# timer_rtc_io.net
KiCad netlist of a schematic drawn in EAGLE
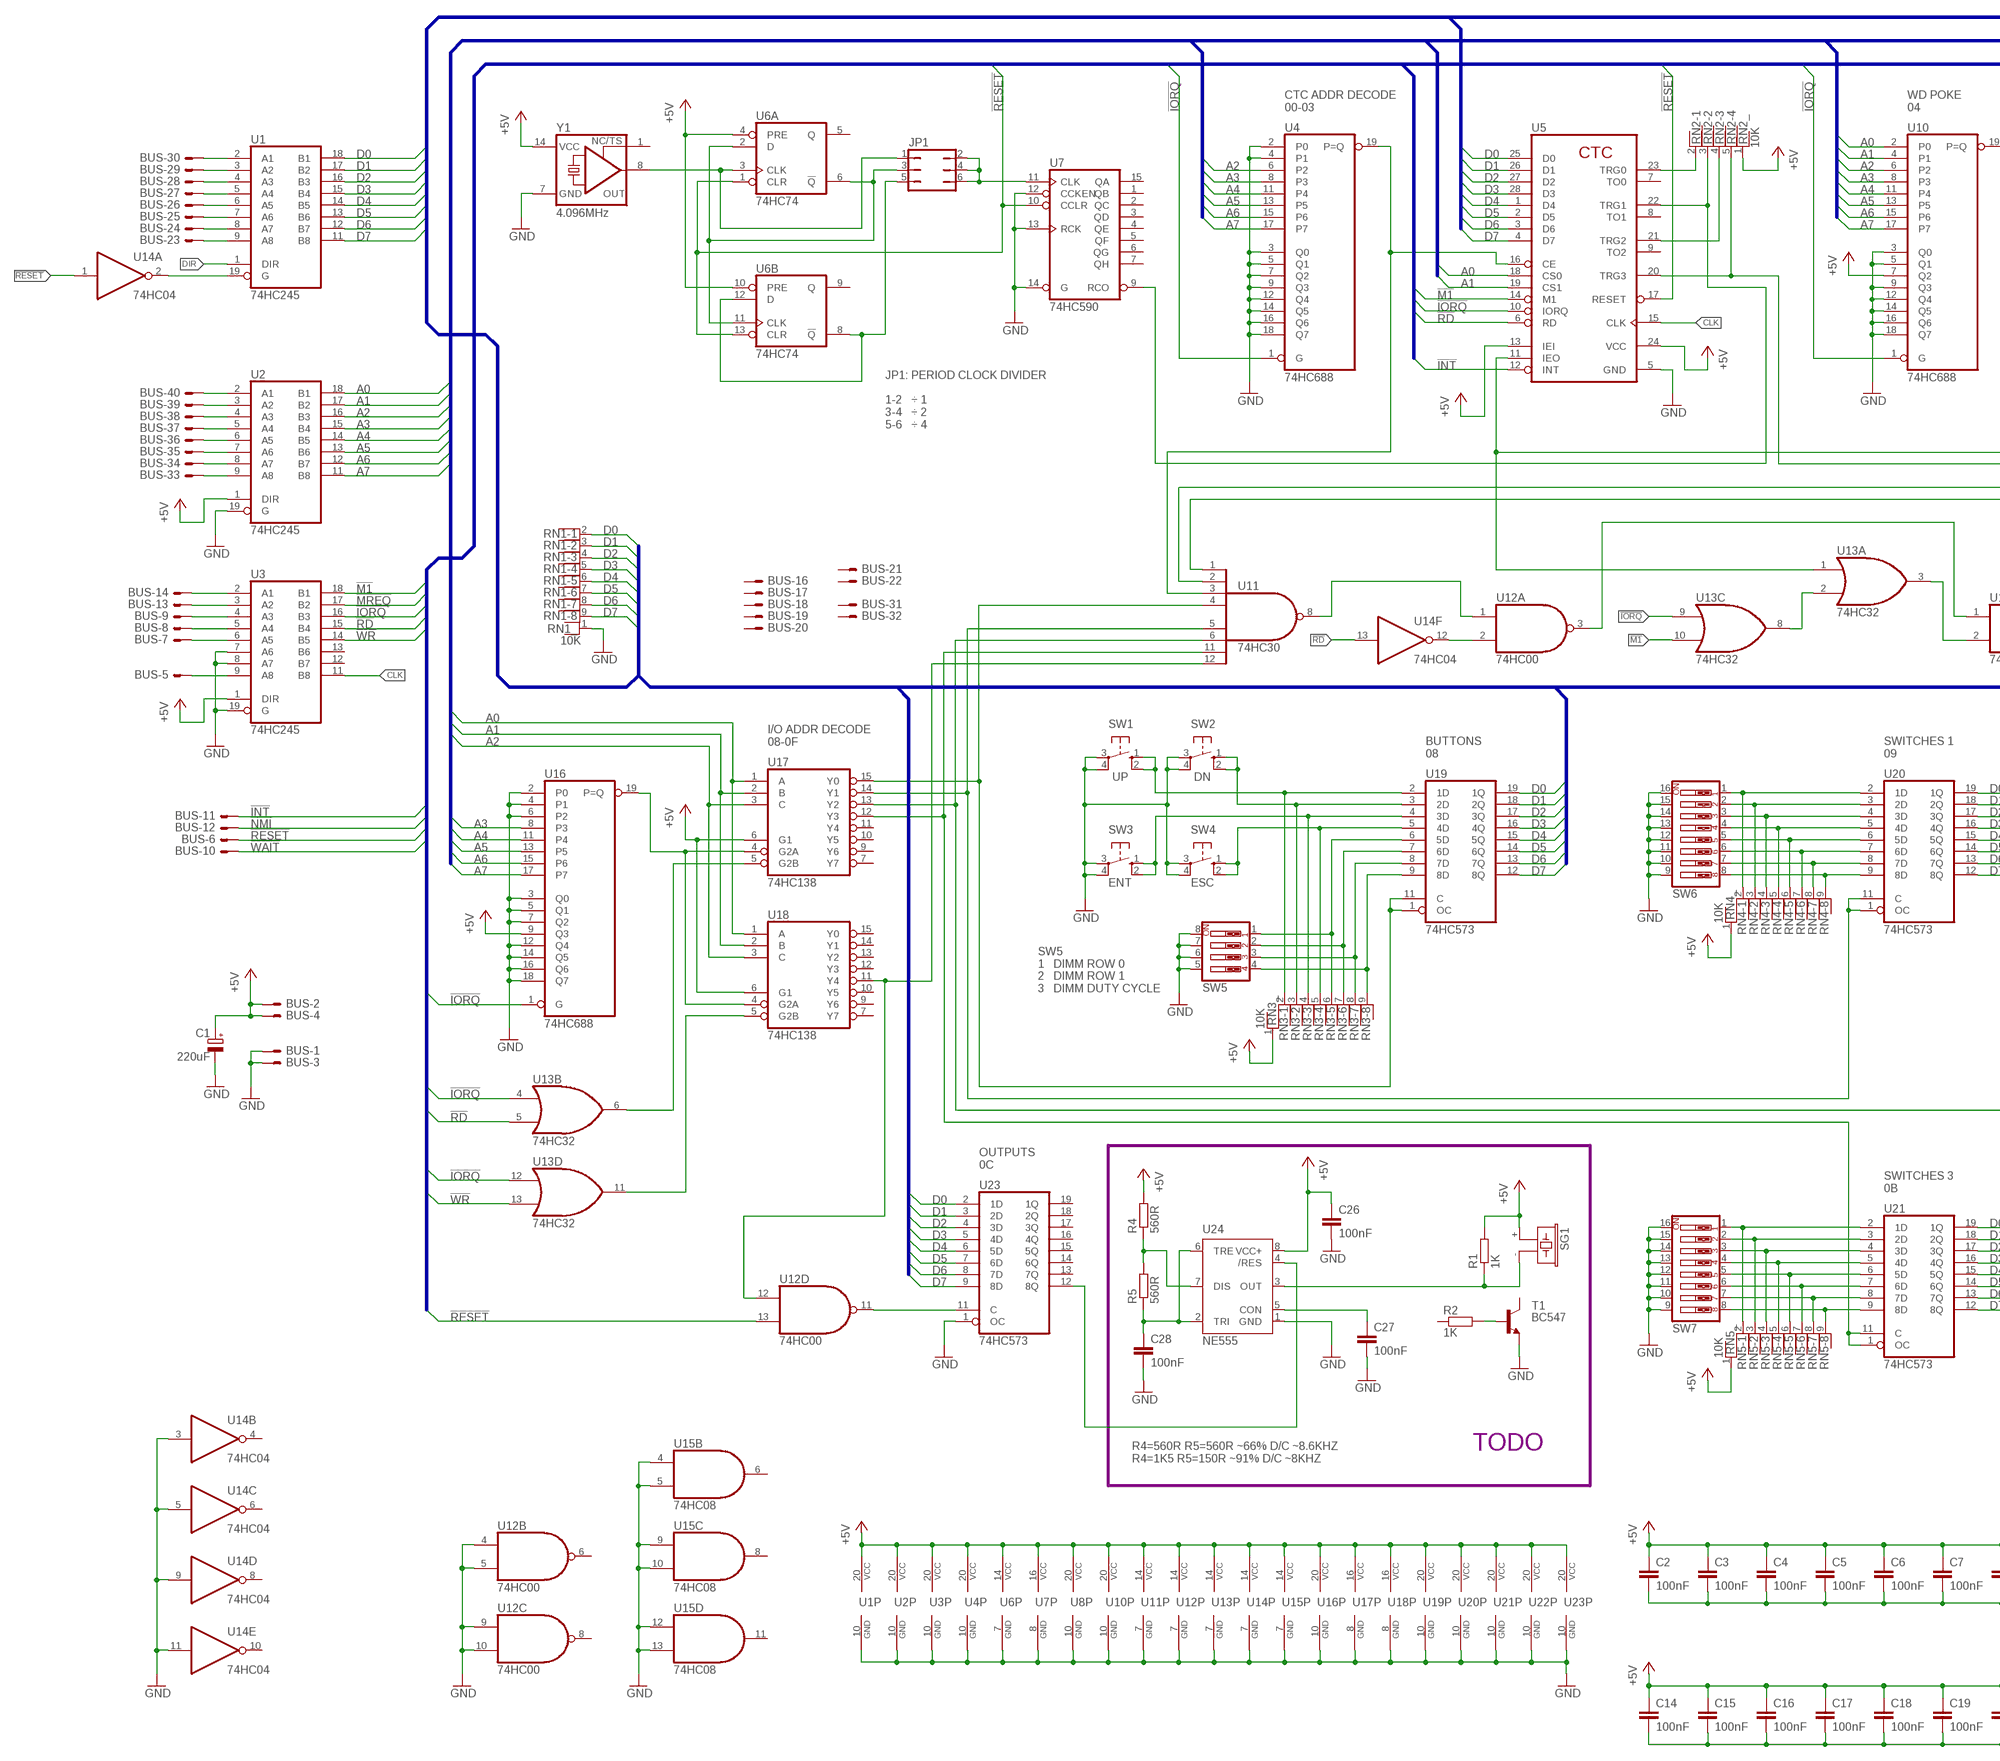
[diagram p0: schematic, sheet 1, part 1 of 2]
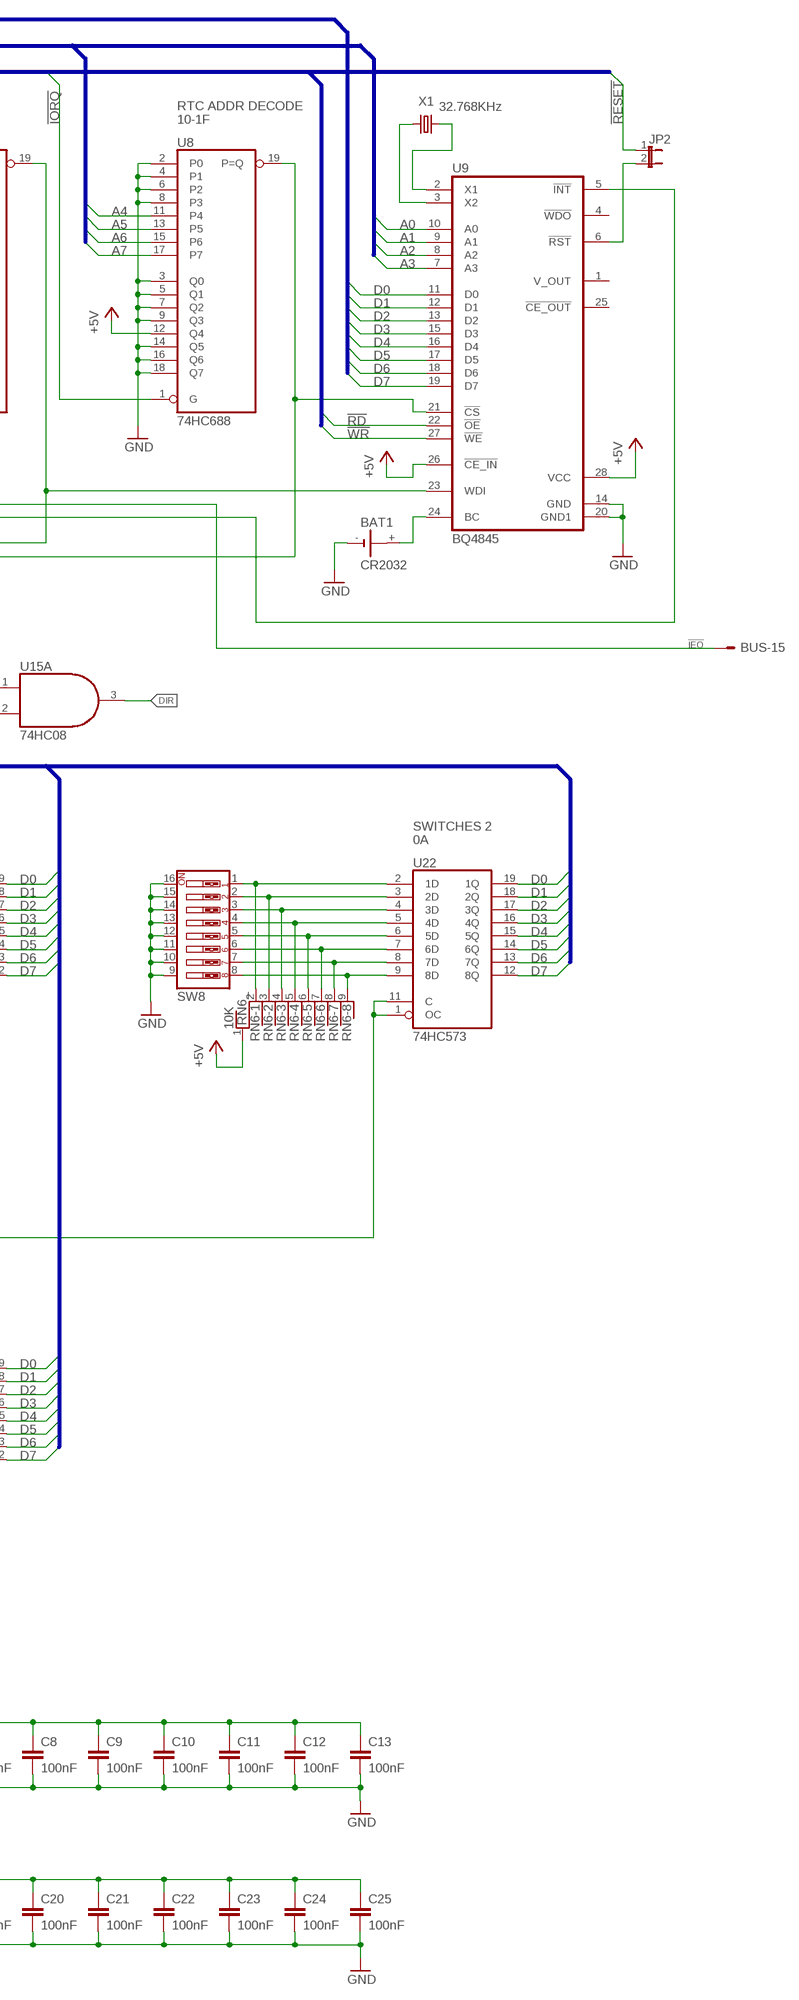
[diagram p1: schematic, sheet 1, part 2 of 2]

(export (version "E")
  (design (tool "Eeschema 10.0.6"))
  (components
    (comp (ref "BAT1")
      (value "CR2032")
      (footprint "eagle-import:CR2032H")
      (libsource (lib "eagle-import") (part "CR2032H"))
    )
    (comp (ref "BUS")
      (value "ML40E")
      (footprint "eagle-import:ML40")
      (libsource (lib "eagle-import") (part "ML40E"))
    )
    (comp (ref "C1")
      (value "220uF")
      (footprint "eagle-import:E3,5-8")
      (libsource (lib "eagle-import") (part "CPOL-EUE3.5-8"))
    )
    (comp (ref "C2")
      (value "100nF")
      (footprint "eagle-import:C050-025X075")
      (libsource (lib "eagle-import") (part "C-EU050-025X075"))
    )
    (comp (ref "C3")
      (value "100nF")
      (footprint "eagle-import:C050-025X075")
      (libsource (lib "eagle-import") (part "C-EU050-025X075"))
    )
    (comp (ref "C4")
      (value "100nF")
      (footprint "eagle-import:C050-025X075")
      (libsource (lib "eagle-import") (part "C-EU050-025X075"))
    )
    (comp (ref "C5")
      (value "100nF")
      (footprint "eagle-import:C050-025X075")
      (libsource (lib "eagle-import") (part "C-EU050-025X075"))
    )
    (comp (ref "C6")
      (value "100nF")
      (footprint "eagle-import:C050-025X075")
      (libsource (lib "eagle-import") (part "C-EU050-025X075"))
    )
    (comp (ref "C7")
      (value "100nF")
      (footprint "eagle-import:C050-025X075")
      (libsource (lib "eagle-import") (part "C-EU050-025X075"))
    )
    (comp (ref "C8")
      (value "100nF")
      (footprint "eagle-import:C050-025X075")
      (libsource (lib "eagle-import") (part "C-EU050-025X075"))
    )
    (comp (ref "C9")
      (value "100nF")
      (footprint "eagle-import:C050-025X075")
      (libsource (lib "eagle-import") (part "C-EU050-025X075"))
    )
    (comp (ref "C10")
      (value "100nF")
      (footprint "eagle-import:C050-025X075")
      (libsource (lib "eagle-import") (part "C-EU050-025X075"))
    )
    (comp (ref "C11")
      (value "100nF")
      (footprint "eagle-import:C050-025X075")
      (libsource (lib "eagle-import") (part "C-EU050-025X075"))
    )
    (comp (ref "C12")
      (value "100nF")
      (footprint "eagle-import:C050-025X075")
      (libsource (lib "eagle-import") (part "C-EU050-025X075"))
    )
    (comp (ref "C13")
      (value "100nF")
      (footprint "eagle-import:C050-025X075")
      (libsource (lib "eagle-import") (part "C-EU050-025X075"))
    )
    (comp (ref "C14")
      (value "100nF")
      (footprint "eagle-import:C050-025X075")
      (libsource (lib "eagle-import") (part "C-EU050-025X075"))
    )
    (comp (ref "C15")
      (value "100nF")
      (footprint "eagle-import:C050-025X075")
      (libsource (lib "eagle-import") (part "C-EU050-025X075"))
    )
    (comp (ref "C16")
      (value "100nF")
      (footprint "eagle-import:C050-025X075")
      (libsource (lib "eagle-import") (part "C-EU050-025X075"))
    )
    (comp (ref "C17")
      (value "100nF")
      (footprint "eagle-import:C050-025X075")
      (libsource (lib "eagle-import") (part "C-EU050-025X075"))
    )
    (comp (ref "C18")
      (value "100nF")
      (footprint "eagle-import:C050-025X075")
      (libsource (lib "eagle-import") (part "C-EU050-025X075"))
    )
    (comp (ref "C19")
      (value "100nF")
      (footprint "eagle-import:C050-025X075")
      (libsource (lib "eagle-import") (part "C-EU050-025X075"))
    )
    (comp (ref "C20")
      (value "100nF")
      (footprint "eagle-import:C050-025X075")
      (libsource (lib "eagle-import") (part "C-EU050-025X075"))
    )
    (comp (ref "C21")
      (value "100nF")
      (footprint "eagle-import:C050-025X075")
      (libsource (lib "eagle-import") (part "C-EU050-025X075"))
    )
    (comp (ref "C22")
      (value "100nF")
      (footprint "eagle-import:C050-025X075")
      (libsource (lib "eagle-import") (part "C-EU050-025X075"))
    )
    (comp (ref "C23")
      (value "100nF")
      (footprint "eagle-import:C050-025X075")
      (libsource (lib "eagle-import") (part "C-EU050-025X075"))
    )
    (comp (ref "C24")
      (value "100nF")
      (footprint "eagle-import:C050-025X075")
      (libsource (lib "eagle-import") (part "C-EU050-025X075"))
    )
    (comp (ref "C25")
      (value "100nF")
      (footprint "eagle-import:C050-025X075")
      (libsource (lib "eagle-import") (part "C-EU050-025X075"))
    )
    (comp (ref "C26")
      (value "100nF")
      (footprint "eagle-import:C050-025X075")
      (libsource (lib "eagle-import") (part "C-EU050-025X075"))
    )
    (comp (ref "C27")
      (value "100nF")
      (footprint "eagle-import:C050-025X075")
      (libsource (lib "eagle-import") (part "C-EU050-025X075"))
    )
    (comp (ref "C28")
      (value "100nF")
      (footprint "eagle-import:C050-025X075")
      (libsource (lib "eagle-import") (part "C-EU050-025X075"))
    )
    (comp (ref "JP1")
      (value "JP3Q")
      (footprint "eagle-import:JP3Q")
      (libsource (lib "eagle-import") (part "JP3Q"))
    )
    (comp (ref "JP2")
      (value "JP1E")
      (footprint "eagle-import:JP1")
      (libsource (lib "eagle-import") (part "JP1E"))
    )
    (comp (ref "R1")
      (value "1K")
      (footprint "eagle-import:0207_10")
      (libsource (lib "eagle-import") (part "R-EU_0207/10"))
    )
    (comp (ref "R2")
      (value "1K")
      (footprint "eagle-import:0207_10")
      (libsource (lib "eagle-import") (part "R-EU_0207/10"))
    )
    (comp (ref "R4")
      (value "560R")
      (footprint "eagle-import:0207_10")
      (libsource (lib "eagle-import") (part "R-EU_0207/10"))
    )
    (comp (ref "R5")
      (value "560R")
      (footprint "eagle-import:0207_10")
      (libsource (lib "eagle-import") (part "R-EU_0207/10"))
    )
    (comp (ref "RN1")
      (value "10K")
      (footprint "eagle-import:RN-9")
      (libsource (lib "eagle-import") (part "RNX8"))
    )
    (comp (ref "RN2")
      (value "10K")
      (footprint "eagle-import:RN-5")
      (libsource (lib "eagle-import") (part "RNX4"))
    )
    (comp (ref "RN3")
      (value "10K")
      (footprint "eagle-import:RN-9")
      (libsource (lib "eagle-import") (part "RNX8"))
    )
    (comp (ref "RN4")
      (value "10K")
      (footprint "eagle-import:RN-9")
      (libsource (lib "eagle-import") (part "RNX8"))
    )
    (comp (ref "RN5")
      (value "10K")
      (footprint "eagle-import:RN-9")
      (libsource (lib "eagle-import") (part "RNX8"))
    )
    (comp (ref "RN6")
      (value "10K")
      (footprint "eagle-import:RN-9")
      (libsource (lib "eagle-import") (part "RNX8"))
    )
    (comp (ref "SG1")
      (value "F/CM12P")
      (footprint "eagle-import:F_CM12P")
      (libsource (lib "eagle-import") (part "F/CM12P"))
    )
    (comp (ref "SW1")
      (value "10-XX")
      (footprint "eagle-import:B3F-10XX")
      (fields (field (name "MPN") "B3F-1000"))
      (libsource (lib "eagle-import") (part "10-XX"))
    )
    (comp (ref "SW2")
      (value "10-XX")
      (footprint "eagle-import:B3F-10XX")
      (fields (field (name "MPN") "B3F-1000"))
      (libsource (lib "eagle-import") (part "10-XX"))
    )
    (comp (ref "SW3")
      (value "10-XX")
      (footprint "eagle-import:B3F-10XX")
      (fields (field (name "MPN") "B3F-1000"))
      (libsource (lib "eagle-import") (part "10-XX"))
    )
    (comp (ref "SW4")
      (value "10-XX")
      (footprint "eagle-import:B3F-10XX")
      (fields (field (name "MPN") "B3F-1000"))
      (libsource (lib "eagle-import") (part "10-XX"))
    )
    (comp (ref "SW5")
      (value "SW_DIP-4")
      (footprint "eagle-import:EDG-04")
      (libsource (lib "eagle-import") (part "SW_DIP-4"))
    )
    (comp (ref "SW6")
      (value "SW_DIP-8")
      (footprint "eagle-import:EDG-08")
      (libsource (lib "eagle-import") (part "SW_DIP-8"))
    )
    (comp (ref "SW7")
      (value "SW_DIP-8")
      (footprint "eagle-import:EDG-08")
      (libsource (lib "eagle-import") (part "SW_DIP-8"))
    )
    (comp (ref "SW8")
      (value "SW_DIP-8")
      (footprint "eagle-import:EDG-08")
      (libsource (lib "eagle-import") (part "SW_DIP-8"))
    )
    (comp (ref "T1")
      (value "BC547")
      (footprint "eagle-import:TO92")
      (libsource (lib "eagle-import") (part "BC547"))
    )
    (comp (ref "U1")
      (value "74HC245")
      (footprint "eagle-import:DIL20")
      (libsource (lib "eagle-import") (part "74245NLS"))
    )
    (comp (ref "U2")
      (value "74HC245")
      (footprint "eagle-import:DIL20")
      (libsource (lib "eagle-import") (part "74245NLS"))
    )
    (comp (ref "U3")
      (value "74HC245")
      (footprint "eagle-import:DIL20")
      (libsource (lib "eagle-import") (part "74245NLS"))
    )
    (comp (ref "U4")
      (value "74HC688")
      (footprint "eagle-import:DIL20")
      (libsource (lib "eagle-import") (part "74688NLS"))
    )
    (comp (ref "U5")
      (value "Z80CTC")
      (footprint "eagle-import:DIL28")
      (libsource (lib "eagle-import") (part "Z80CTC"))
    )
    (comp (ref "U6")
      (value "74HC74")
      (footprint "eagle-import:DIL14")
      (libsource (lib "eagle-import") (part "7474NLS"))
    )
    (comp (ref "U7")
      (value "74HC590")
      (footprint "eagle-import:DIL16")
      (libsource (lib "eagle-import") (part "74590NLS"))
    )
    (comp (ref "U8")
      (value "74HC688")
      (footprint "eagle-import:DIL20")
      (libsource (lib "eagle-import") (part "74688NLS"))
    )
    (comp (ref "U9")
      (value "BQ4845")
      (footprint "eagle-import:DIL28-6")
      (libsource (lib "eagle-import") (part "BQ4845P"))
    )
    (comp (ref "U10")
      (value "74HC688")
      (footprint "eagle-import:DIL20")
      (libsource (lib "eagle-import") (part "74688NLS"))
    )
    (comp (ref "U11")
      (value "74HC30")
      (footprint "eagle-import:DIL14")
      (libsource (lib "eagle-import") (part "7430NLS"))
    )
    (comp (ref "U12")
      (value "74HC00")
      (footprint "eagle-import:DIL14")
      (libsource (lib "eagle-import") (part "7400NLS"))
    )
    (comp (ref "U13")
      (value "74HC32")
      (footprint "eagle-import:DIL14")
      (libsource (lib "eagle-import") (part "7432NLS"))
    )
    (comp (ref "U14")
      (value "74HC04")
      (footprint "eagle-import:DIL14")
      (libsource (lib "eagle-import") (part "7404NLS"))
    )
    (comp (ref "U15")
      (value "74HC08")
      (footprint "eagle-import:DIL14")
      (libsource (lib "eagle-import") (part "7408NLS"))
    )
    (comp (ref "U16")
      (value "74HC688")
      (footprint "eagle-import:DIL20")
      (libsource (lib "eagle-import") (part "74688NLS"))
    )
    (comp (ref "U17")
      (value "74HC138")
      (footprint "eagle-import:DIL16")
      (libsource (lib "eagle-import") (part "74138NLS"))
    )
    (comp (ref "U18")
      (value "74HC138")
      (footprint "eagle-import:DIL16")
      (libsource (lib "eagle-import") (part "74138NLS"))
    )
    (comp (ref "U19")
      (value "74HC573")
      (footprint "eagle-import:DIL20")
      (libsource (lib "eagle-import") (part "74573NHC"))
    )
    (comp (ref "U20")
      (value "74HC573")
      (footprint "eagle-import:DIL20")
      (libsource (lib "eagle-import") (part "74573NHC"))
    )
    (comp (ref "U21")
      (value "74HC573")
      (footprint "eagle-import:DIL20")
      (libsource (lib "eagle-import") (part "74573NHC"))
    )
    (comp (ref "U22")
      (value "74HC573")
      (footprint "eagle-import:DIL20")
      (libsource (lib "eagle-import") (part "74573NHC"))
    )
    (comp (ref "U23")
      (value "74HC573")
      (footprint "eagle-import:DIL20")
      (libsource (lib "eagle-import") (part "74573NHC"))
    )
    (comp (ref "U24")
      (value "NE555")
      (footprint "eagle-import:DIL-08")
      (fields (field (name "MF") "Arrow Electronics") (field (name "MPN") "NE555N"))
      (libsource (lib "eagle-import") (part "NE555"))
    )
    (comp (ref "X1")
      (value "32.768KHz")
      (footprint "eagle-import:TC38H")
      (libsource (lib "eagle-import") (part "CRYSTALTC38H"))
    )
    (comp (ref "Y1")
      (value "4.096MHz")
      (footprint "eagle-import:DIL14S")
      (libsource (lib "eagle-import") (part "XO-14"))
    )
  )
  (nets
    (net (code "29") (name "+5V") (class "Default")
      (node (ref "BUS") (pin "2") (pinfunction "S_2") (pintype "passive"))
      (node (ref "BUS") (pin "4") (pinfunction "S_4") (pintype "passive"))
      (node (ref "C1") (pin "+") (pinfunction "+_+") (pintype "passive"))
      (node (ref "C10") (pin "1") (pinfunction "1_1") (pintype "passive"))
      (node (ref "C11") (pin "1") (pinfunction "1_1") (pintype "passive"))
      (node (ref "C12") (pin "1") (pinfunction "1_1") (pintype "passive"))
      (node (ref "C13") (pin "1") (pinfunction "1_1") (pintype "passive"))
      (node (ref "C14") (pin "1") (pinfunction "1_1") (pintype "passive"))
      (node (ref "C15") (pin "1") (pinfunction "1_1") (pintype "passive"))
      (node (ref "C16") (pin "1") (pinfunction "1_1") (pintype "passive"))
      (node (ref "C17") (pin "1") (pinfunction "1_1") (pintype "passive"))
      (node (ref "C18") (pin "1") (pinfunction "1_1") (pintype "passive"))
      (node (ref "C19") (pin "1") (pinfunction "1_1") (pintype "passive"))
      (node (ref "C2") (pin "1") (pinfunction "1_1") (pintype "passive"))
      (node (ref "C20") (pin "1") (pinfunction "1_1") (pintype "passive"))
      (node (ref "C21") (pin "1") (pinfunction "1_1") (pintype "passive"))
      (node (ref "C22") (pin "1") (pinfunction "1_1") (pintype "passive"))
      (node (ref "C23") (pin "1") (pinfunction "1_1") (pintype "passive"))
      (node (ref "C24") (pin "1") (pinfunction "1_1") (pintype "passive"))
      (node (ref "C25") (pin "1") (pinfunction "1_1") (pintype "passive"))
      (node (ref "C26") (pin "1") (pinfunction "1_1") (pintype "passive"))
      (node (ref "C3") (pin "1") (pinfunction "1_1") (pintype "passive"))
      (node (ref "C4") (pin "1") (pinfunction "1_1") (pintype "passive"))
      (node (ref "C5") (pin "1") (pinfunction "1_1") (pintype "passive"))
      (node (ref "C6") (pin "1") (pinfunction "1_1") (pintype "passive"))
      (node (ref "C7") (pin "1") (pinfunction "1_1") (pintype "passive"))
      (node (ref "C8") (pin "1") (pinfunction "1_1") (pintype "passive"))
      (node (ref "C9") (pin "1") (pinfunction "1_1") (pintype "passive"))
      (node (ref "R1") (pin "2") (pinfunction "2_2") (pintype "passive"))
      (node (ref "R4") (pin "2") (pinfunction "2_2") (pintype "passive"))
      (node (ref "RN2") (pin "1") (pinfunction "1_1") (pintype "passive"))
      (node (ref "RN3") (pin "1") (pinfunction "1_1") (pintype "passive"))
      (node (ref "RN4") (pin "1") (pinfunction "1_1") (pintype "passive"))
      (node (ref "RN5") (pin "1") (pinfunction "1_1") (pintype "passive"))
      (node (ref "RN6") (pin "1") (pinfunction "1_1") (pintype "passive"))
      (node (ref "SG1") (pin "+") (pinfunction "1_+") (pintype "passive"))
      (node (ref "U1") (pin "20") (pinfunction "VCC_20") (pintype "power_in"))
      (node (ref "U10") (pin "20") (pinfunction "VCC_20") (pintype "power_in"))
      (node (ref "U10") (pin "7") (pinfunction "Q2_7") (pintype "input"))
      (node (ref "U11") (pin "14") (pinfunction "VCC_14") (pintype "power_in"))
      (node (ref "U12") (pin "14") (pinfunction "VCC_14") (pintype "power_in"))
      (node (ref "U13") (pin "14") (pinfunction "VCC_14") (pintype "power_in"))
      (node (ref "U14") (pin "14") (pinfunction "VCC_14") (pintype "power_in"))
      (node (ref "U15") (pin "14") (pinfunction "VCC_14") (pintype "power_in"))
      (node (ref "U16") (pin "20") (pinfunction "VCC_20") (pintype "power_in"))
      (node (ref "U16") (pin "9") (pinfunction "Q3_9") (pintype "input"))
      (node (ref "U17") (pin "16") (pinfunction "VCC_16") (pintype "power_in"))
      (node (ref "U17") (pin "6") (pinfunction "G1_6") (pintype "input"))
      (node (ref "U18") (pin "16") (pinfunction "VCC_16") (pintype "power_in"))
      (node (ref "U18") (pin "6") (pinfunction "G1_6") (pintype "input"))
      (node (ref "U19") (pin "20") (pinfunction "VCC_20") (pintype "power_in"))
      (node (ref "U2") (pin "1") (pinfunction "DIR_1") (pintype "input"))
      (node (ref "U2") (pin "20") (pinfunction "VCC_20") (pintype "power_in"))
      (node (ref "U20") (pin "20") (pinfunction "VCC_20") (pintype "power_in"))
      (node (ref "U21") (pin "20") (pinfunction "VCC_20") (pintype "power_in"))
      (node (ref "U22") (pin "20") (pinfunction "VCC_20") (pintype "power_in"))
      (node (ref "U23") (pin "20") (pinfunction "VCC_20") (pintype "power_in"))
      (node (ref "U24") (pin "8") (pinfunction "VCC+_8") (pintype "power_in"))
      (node (ref "U3") (pin "1") (pinfunction "DIR_1") (pintype "input"))
      (node (ref "U3") (pin "20") (pinfunction "VCC_20") (pintype "power_in"))
      (node (ref "U4") (pin "20") (pinfunction "VCC_20") (pintype "power_in"))
      (node (ref "U5") (pin "13") (pinfunction "IEI_13") (pintype "input"))
      (node (ref "U5") (pin "24") (pinfunction "VCC_24") (pintype "power_in"))
      (node (ref "U6") (pin "10") (pinfunction "PRE_10") (pintype "input"))
      (node (ref "U6") (pin "14") (pinfunction "VCC_14") (pintype "power_in"))
      (node (ref "U6") (pin "4") (pinfunction "PRE_4") (pintype "input"))
      (node (ref "U7") (pin "16") (pinfunction "VCC_16") (pintype "power_in"))
      (node (ref "U8") (pin "12") (pinfunction "Q4_12") (pintype "input"))
      (node (ref "U8") (pin "20") (pinfunction "VCC_20") (pintype "power_in"))
      (node (ref "U9") (pin "26") (pinfunction "~{CE_IN}_26") (pintype "input"))
      (node (ref "U9") (pin "28") (pinfunction "VCC_28") (pintype "power_in"))
      (node (ref "Y1") (pin "14") (pinfunction "VCC_14") (pintype "power_in"))
    )
    (net (code "30") (name "/A0") (class "Default")
      (node (ref "U10") (pin "2") (pinfunction "P0_2") (pintype "input"))
      (node (ref "U17") (pin "1") (pinfunction "A_1") (pintype "input"))
      (node (ref "U18") (pin "1") (pinfunction "A_1") (pintype "input"))
      (node (ref "U2") (pin "18") (pinfunction "B1_18") (pintype "bidirectional"))
      (node (ref "U5") (pin "18") (pinfunction "CS0_18") (pintype "input"))
      (node (ref "U9") (pin "10") (pinfunction "A0_10") (pintype "input"))
    )
    (net (code "31") (name "/A1") (class "Default")
      (node (ref "U10") (pin "4") (pinfunction "P1_4") (pintype "input"))
      (node (ref "U17") (pin "2") (pinfunction "B_2") (pintype "input"))
      (node (ref "U18") (pin "2") (pinfunction "B_2") (pintype "input"))
      (node (ref "U2") (pin "17") (pinfunction "B2_17") (pintype "bidirectional"))
      (node (ref "U5") (pin "19") (pinfunction "CS1_19") (pintype "input"))
      (node (ref "U9") (pin "9") (pinfunction "A1_9") (pintype "input"))
    )
    (net (code "32") (name "/A2") (class "Default")
      (node (ref "U10") (pin "6") (pinfunction "P2_6") (pintype "input"))
      (node (ref "U17") (pin "3") (pinfunction "C_3") (pintype "input"))
      (node (ref "U18") (pin "3") (pinfunction "C_3") (pintype "input"))
      (node (ref "U2") (pin "16") (pinfunction "B3_16") (pintype "bidirectional"))
      (node (ref "U4") (pin "6") (pinfunction "P2_6") (pintype "input"))
      (node (ref "U9") (pin "8") (pinfunction "A2_8") (pintype "input"))
    )
    (net (code "33") (name "/A3") (class "Default")
      (node (ref "U10") (pin "8") (pinfunction "P3_8") (pintype "input"))
      (node (ref "U16") (pin "8") (pinfunction "P3_8") (pintype "input"))
      (node (ref "U2") (pin "15") (pinfunction "B4_15") (pintype "bidirectional"))
      (node (ref "U4") (pin "8") (pinfunction "P3_8") (pintype "input"))
      (node (ref "U9") (pin "7") (pinfunction "A3_7") (pintype "input"))
    )
    (net (code "34") (name "/A4") (class "Default")
      (node (ref "U10") (pin "11") (pinfunction "P4_11") (pintype "input"))
      (node (ref "U16") (pin "11") (pinfunction "P4_11") (pintype "input"))
      (node (ref "U2") (pin "14") (pinfunction "B5_14") (pintype "bidirectional"))
      (node (ref "U4") (pin "11") (pinfunction "P4_11") (pintype "input"))
      (node (ref "U8") (pin "11") (pinfunction "P4_11") (pintype "input"))
    )
    (net (code "35") (name "/A5") (class "Default")
      (node (ref "U10") (pin "13") (pinfunction "P5_13") (pintype "input"))
      (node (ref "U16") (pin "13") (pinfunction "P5_13") (pintype "input"))
      (node (ref "U2") (pin "13") (pinfunction "B6_13") (pintype "bidirectional"))
      (node (ref "U4") (pin "13") (pinfunction "P5_13") (pintype "input"))
      (node (ref "U8") (pin "13") (pinfunction "P5_13") (pintype "input"))
    )
    (net (code "36") (name "/A6") (class "Default")
      (node (ref "U10") (pin "15") (pinfunction "P6_15") (pintype "input"))
      (node (ref "U16") (pin "15") (pinfunction "P6_15") (pintype "input"))
      (node (ref "U2") (pin "12") (pinfunction "B7_12") (pintype "bidirectional"))
      (node (ref "U4") (pin "15") (pinfunction "P6_15") (pintype "input"))
      (node (ref "U8") (pin "15") (pinfunction "P6_15") (pintype "input"))
    )
    (net (code "37") (name "/D0") (class "Default")
      (node (ref "RN1") (pin "2") (pinfunction "1_2") (pintype "passive"))
      (node (ref "U1") (pin "18") (pinfunction "B1_18") (pintype "bidirectional"))
      (node (ref "U19") (pin "19") (pinfunction "1Q_19") (pintype "tri_state"))
      (node (ref "U20") (pin "19") (pinfunction "1Q_19") (pintype "tri_state"))
      (node (ref "U21") (pin "19") (pinfunction "1Q_19") (pintype "tri_state"))
      (node (ref "U22") (pin "19") (pinfunction "1Q_19") (pintype "tri_state"))
      (node (ref "U23") (pin "2") (pinfunction "1D_2") (pintype "input"))
      (node (ref "U5") (pin "25") (pinfunction "D0_25") (pintype "bidirectional"))
      (node (ref "U9") (pin "11") (pinfunction "D0_11") (pintype "bidirectional"))
    )
    (net (code "38") (name "/D1") (class "Default")
      (node (ref "RN1") (pin "3") (pinfunction "1_3") (pintype "passive"))
      (node (ref "U1") (pin "17") (pinfunction "B2_17") (pintype "bidirectional"))
      (node (ref "U19") (pin "18") (pinfunction "2Q_18") (pintype "tri_state"))
      (node (ref "U20") (pin "18") (pinfunction "2Q_18") (pintype "tri_state"))
      (node (ref "U21") (pin "18") (pinfunction "2Q_18") (pintype "tri_state"))
      (node (ref "U22") (pin "18") (pinfunction "2Q_18") (pintype "tri_state"))
      (node (ref "U23") (pin "3") (pinfunction "2D_3") (pintype "input"))
      (node (ref "U5") (pin "26") (pinfunction "D1_26") (pintype "bidirectional"))
      (node (ref "U9") (pin "12") (pinfunction "D1_12") (pintype "bidirectional"))
    )
    (net (code "39") (name "/D2") (class "Default")
      (node (ref "RN1") (pin "4") (pinfunction "1_4") (pintype "passive"))
      (node (ref "U1") (pin "16") (pinfunction "B3_16") (pintype "bidirectional"))
      (node (ref "U19") (pin "17") (pinfunction "3Q_17") (pintype "tri_state"))
      (node (ref "U20") (pin "17") (pinfunction "3Q_17") (pintype "tri_state"))
      (node (ref "U21") (pin "17") (pinfunction "3Q_17") (pintype "tri_state"))
      (node (ref "U22") (pin "17") (pinfunction "3Q_17") (pintype "tri_state"))
      (node (ref "U23") (pin "4") (pinfunction "3D_4") (pintype "input"))
      (node (ref "U5") (pin "27") (pinfunction "D2_27") (pintype "bidirectional"))
      (node (ref "U9") (pin "13") (pinfunction "D2_13") (pintype "bidirectional"))
    )
    (net (code "40") (name "/D3") (class "Default")
      (node (ref "RN1") (pin "5") (pinfunction "1_5") (pintype "passive"))
      (node (ref "U1") (pin "15") (pinfunction "B4_15") (pintype "bidirectional"))
      (node (ref "U19") (pin "16") (pinfunction "4Q_16") (pintype "tri_state"))
      (node (ref "U20") (pin "16") (pinfunction "4Q_16") (pintype "tri_state"))
      (node (ref "U21") (pin "16") (pinfunction "4Q_16") (pintype "tri_state"))
      (node (ref "U22") (pin "16") (pinfunction "4Q_16") (pintype "tri_state"))
      (node (ref "U23") (pin "5") (pinfunction "4D_5") (pintype "input"))
      (node (ref "U5") (pin "28") (pinfunction "D3_28") (pintype "bidirectional"))
      (node (ref "U9") (pin "15") (pinfunction "D3_15") (pintype "bidirectional"))
    )
    (net (code "41") (name "/D4") (class "Default")
      (node (ref "RN1") (pin "6") (pinfunction "1_6") (pintype "passive"))
      (node (ref "U1") (pin "14") (pinfunction "B5_14") (pintype "bidirectional"))
      (node (ref "U19") (pin "15") (pinfunction "5Q_15") (pintype "tri_state"))
      (node (ref "U20") (pin "15") (pinfunction "5Q_15") (pintype "tri_state"))
      (node (ref "U21") (pin "15") (pinfunction "5Q_15") (pintype "tri_state"))
      (node (ref "U22") (pin "15") (pinfunction "5Q_15") (pintype "tri_state"))
      (node (ref "U23") (pin "6") (pinfunction "5D_6") (pintype "input"))
      (node (ref "U5") (pin "1") (pinfunction "D4_1") (pintype "bidirectional"))
      (node (ref "U9") (pin "16") (pinfunction "D4_16") (pintype "bidirectional"))
    )
    (net (code "42") (name "/D5") (class "Default")
      (node (ref "RN1") (pin "7") (pinfunction "1_7") (pintype "passive"))
      (node (ref "U1") (pin "13") (pinfunction "B6_13") (pintype "bidirectional"))
      (node (ref "U19") (pin "14") (pinfunction "6Q_14") (pintype "tri_state"))
      (node (ref "U20") (pin "14") (pinfunction "6Q_14") (pintype "tri_state"))
      (node (ref "U21") (pin "14") (pinfunction "6Q_14") (pintype "tri_state"))
      (node (ref "U22") (pin "14") (pinfunction "6Q_14") (pintype "tri_state"))
      (node (ref "U23") (pin "7") (pinfunction "6D_7") (pintype "input"))
      (node (ref "U5") (pin "2") (pinfunction "D5_2") (pintype "bidirectional"))
      (node (ref "U9") (pin "17") (pinfunction "D5_17") (pintype "bidirectional"))
    )
    (net (code "43") (name "/D6") (class "Default")
      (node (ref "RN1") (pin "8") (pinfunction "1_8") (pintype "passive"))
      (node (ref "U1") (pin "12") (pinfunction "B7_12") (pintype "bidirectional"))
      (node (ref "U19") (pin "13") (pinfunction "7Q_13") (pintype "tri_state"))
      (node (ref "U20") (pin "13") (pinfunction "7Q_13") (pintype "tri_state"))
      (node (ref "U21") (pin "13") (pinfunction "7Q_13") (pintype "tri_state"))
      (node (ref "U22") (pin "13") (pinfunction "7Q_13") (pintype "tri_state"))
      (node (ref "U23") (pin "8") (pinfunction "7D_8") (pintype "input"))
      (node (ref "U5") (pin "3") (pinfunction "D6_3") (pintype "bidirectional"))
      (node (ref "U9") (pin "18") (pinfunction "D6_18") (pintype "bidirectional"))
    )
    (net (code "44") (name "/D7") (class "Default")
      (node (ref "RN1") (pin "9") (pinfunction "1_9") (pintype "passive"))
      (node (ref "U1") (pin "11") (pinfunction "B8_11") (pintype "bidirectional"))
      (node (ref "U19") (pin "12") (pinfunction "8Q_12") (pintype "tri_state"))
      (node (ref "U20") (pin "12") (pinfunction "8Q_12") (pintype "tri_state"))
      (node (ref "U21") (pin "12") (pinfunction "8Q_12") (pintype "tri_state"))
      (node (ref "U22") (pin "12") (pinfunction "8Q_12") (pintype "tri_state"))
      (node (ref "U23") (pin "9") (pinfunction "8D_9") (pintype "input"))
      (node (ref "U5") (pin "4") (pinfunction "D7_4") (pintype "bidirectional"))
      (node (ref "U9") (pin "19") (pinfunction "D7_19") (pintype "bidirectional"))
    )
    (net (code "45") (name "/Z80ADDRESS:A0") (class "Default")
      (node (ref "U10") (pin "17") (pinfunction "P7_17") (pintype "input"))
      (node (ref "U16") (pin "17") (pinfunction "P7_17") (pintype "input"))
      (node (ref "U2") (pin "11") (pinfunction "B8_11") (pintype "bidirectional"))
      (node (ref "U4") (pin "17") (pinfunction "P7_17") (pintype "input"))
      (node (ref "U8") (pin "17") (pinfunction "P7_17") (pintype "input"))
    )
    (net (code "49") (name "/~{IEO}") (class "Default")
      (node (ref "BUS") (pin "15") (pinfunction "S_15") (pintype "passive"))
      (node (ref "U13") (pin "1") (pinfunction "I0_1") (pintype "input"))
      (node (ref "U5") (pin "11") (pinfunction "IEO_11") (pintype "output"))
    )
    (net (code "50") (name "/~{INT}") (class "Default")
      (node (ref "BUS") (pin "11") (pinfunction "S_11") (pintype "passive"))
      (node (ref "U5") (pin "12") (pinfunction "INT_12") (pintype "output"))
    )
    (net (code "51") (name "/~{IORQ}") (class "Default")
      (node (ref "U10") (pin "1") (pinfunction "G_1") (pintype "input"))
      (node (ref "U13") (pin "12") (pinfunction "I0_12") (pintype "input"))
      (node (ref "U13") (pin "4") (pinfunction "I0_4") (pintype "input"))
      (node (ref "U13") (pin "9") (pinfunction "I0_9") (pintype "input"))
      (node (ref "U16") (pin "1") (pinfunction "G_1") (pintype "input"))
      (node (ref "U3") (pin "16") (pinfunction "B3_16") (pintype "bidirectional"))
      (node (ref "U4") (pin "1") (pinfunction "G_1") (pintype "input"))
      (node (ref "U5") (pin "10") (pinfunction "IORQ_10") (pintype "input"))
      (node (ref "U8") (pin "1") (pinfunction "G_1") (pintype "input"))
    )
    (net (code "52") (name "/~{M1}") (class "Default")
      (node (ref "U13") (pin "10") (pinfunction "I1_10") (pintype "input"))
      (node (ref "U3") (pin "18") (pinfunction "B1_18") (pintype "bidirectional"))
      (node (ref "U5") (pin "14") (pinfunction "M1_14") (pintype "input"))
    )
    (net (code "53") (name "/~{MREQ}") (class "Default")
      (node (ref "U3") (pin "17") (pinfunction "B2_17") (pintype "bidirectional"))
    )
    (net (code "54") (name "/~{NMI}") (class "Default")
      (node (ref "BUS") (pin "12") (pinfunction "S_12") (pintype "passive"))
    )
    (net (code "55") (name "/~{RD}") (class "Default")
      (node (ref "U13") (pin "5") (pinfunction "I1_5") (pintype "input"))
      (node (ref "U14") (pin "13") (pinfunction "I_13") (pintype "input"))
      (node (ref "U3") (pin "15") (pinfunction "B4_15") (pintype "bidirectional"))
      (node (ref "U5") (pin "6") (pinfunction "RD_6") (pintype "input"))
      (node (ref "U9") (pin "22") (pinfunction "~{OE}_22") (pintype "input"))
    )
    (net (code "56") (name "/~{RESET}") (class "Default")
      (node (ref "BUS") (pin "6") (pinfunction "S_6") (pintype "passive"))
      (node (ref "JP2") (pin "1") (pinfunction "1_1") (pintype "passive"))
      (node (ref "U12") (pin "13") (pinfunction "I1_13") (pintype "input"))
      (node (ref "U14") (pin "1") (pinfunction "I_1") (pintype "input"))
      (node (ref "U5") (pin "17") (pinfunction "RESET_17") (pintype "input"))
      (node (ref "U6") (pin "1") (pinfunction "CLR_1") (pintype "input"))
      (node (ref "U6") (pin "13") (pinfunction "CLR_13") (pintype "input"))
      (node (ref "U7") (pin "10") (pinfunction "CCLR_10") (pintype "input"))
    )
    (net (code "57") (name "/~{WAIT}") (class "Default")
      (node (ref "BUS") (pin "10") (pinfunction "S_10") (pintype "passive"))
    )
    (net (code "58") (name "/~{WR}") (class "Default")
      (node (ref "U13") (pin "13") (pinfunction "I1_13") (pintype "input"))
      (node (ref "U3") (pin "14") (pinfunction "B5_14") (pintype "bidirectional"))
      (node (ref "U9") (pin "27") (pinfunction "~{WE}_27") (pintype "input"))
    )
    (net (code "59") (name "CLK") (class "Default")
      (node (ref "U3") (pin "11") (pinfunction "B8_11") (pintype "bidirectional"))
      (node (ref "U5") (pin "15") (pinfunction "CLK_15") (pintype "input"))
    )
    (net (code "60") (name "DIR") (class "Default")
      (node (ref "U1") (pin "1") (pinfunction "DIR_1") (pintype "input"))
      (node (ref "U15") (pin "3") (pinfunction "O_3") (pintype "output"))
    )
    (net (code "61") (name "GND") (class "Default")
      (node (ref "BAT1") (pin "-") (pinfunction "-_-") (pintype "passive"))
      (node (ref "BUS") (pin "1") (pinfunction "S_1") (pintype "passive"))
      (node (ref "BUS") (pin "3") (pinfunction "S_3") (pintype "passive"))
      (node (ref "C1") (pin "-") (pinfunction "-_-") (pintype "passive"))
      (node (ref "C10") (pin "2") (pinfunction "2_2") (pintype "passive"))
      (node (ref "C11") (pin "2") (pinfunction "2_2") (pintype "passive"))
      (node (ref "C12") (pin "2") (pinfunction "2_2") (pintype "passive"))
      (node (ref "C13") (pin "2") (pinfunction "2_2") (pintype "passive"))
      (node (ref "C14") (pin "2") (pinfunction "2_2") (pintype "passive"))
      (node (ref "C15") (pin "2") (pinfunction "2_2") (pintype "passive"))
      (node (ref "C16") (pin "2") (pinfunction "2_2") (pintype "passive"))
      (node (ref "C17") (pin "2") (pinfunction "2_2") (pintype "passive"))
      (node (ref "C18") (pin "2") (pinfunction "2_2") (pintype "passive"))
      (node (ref "C19") (pin "2") (pinfunction "2_2") (pintype "passive"))
      (node (ref "C2") (pin "2") (pinfunction "2_2") (pintype "passive"))
      (node (ref "C20") (pin "2") (pinfunction "2_2") (pintype "passive"))
      (node (ref "C21") (pin "2") (pinfunction "2_2") (pintype "passive"))
      (node (ref "C22") (pin "2") (pinfunction "2_2") (pintype "passive"))
      (node (ref "C23") (pin "2") (pinfunction "2_2") (pintype "passive"))
      (node (ref "C24") (pin "2") (pinfunction "2_2") (pintype "passive"))
      (node (ref "C25") (pin "2") (pinfunction "2_2") (pintype "passive"))
      (node (ref "C26") (pin "2") (pinfunction "2_2") (pintype "passive"))
      (node (ref "C27") (pin "2") (pinfunction "2_2") (pintype "passive"))
      (node (ref "C28") (pin "2") (pinfunction "2_2") (pintype "passive"))
      (node (ref "C3") (pin "2") (pinfunction "2_2") (pintype "passive"))
      (node (ref "C4") (pin "2") (pinfunction "2_2") (pintype "passive"))
      (node (ref "C5") (pin "2") (pinfunction "2_2") (pintype "passive"))
      (node (ref "C6") (pin "2") (pinfunction "2_2") (pintype "passive"))
      (node (ref "C7") (pin "2") (pinfunction "2_2") (pintype "passive"))
      (node (ref "C8") (pin "2") (pinfunction "2_2") (pintype "passive"))
      (node (ref "C9") (pin "2") (pinfunction "2_2") (pintype "passive"))
      (node (ref "RN1") (pin "1") (pinfunction "1_1") (pintype "passive"))
      (node (ref "SW1") (pin "3") (pinfunction "P_3") (pintype "passive"))
      (node (ref "SW1") (pin "4") (pinfunction "P1_4") (pintype "passive"))
      (node (ref "SW2") (pin "3") (pinfunction "P_3") (pintype "passive"))
      (node (ref "SW2") (pin "4") (pinfunction "P1_4") (pintype "passive"))
      (node (ref "SW3") (pin "3") (pinfunction "P_3") (pintype "passive"))
      (node (ref "SW3") (pin "4") (pinfunction "P1_4") (pintype "passive"))
      (node (ref "SW4") (pin "3") (pinfunction "P_3") (pintype "passive"))
      (node (ref "SW4") (pin "4") (pinfunction "P1_4") (pintype "passive"))
      (node (ref "SW5") (pin "5") (pinfunction "5_5") (pintype "passive"))
      (node (ref "SW5") (pin "6") (pinfunction "6_6") (pintype "passive"))
      (node (ref "SW5") (pin "7") (pinfunction "7_7") (pintype "passive"))
      (node (ref "SW5") (pin "8") (pinfunction "8_8") (pintype "passive"))
      (node (ref "SW6") (pin "10") (pinfunction "10_10") (pintype "passive"))
      (node (ref "SW6") (pin "11") (pinfunction "11_11") (pintype "passive"))
      (node (ref "SW6") (pin "12") (pinfunction "12_12") (pintype "passive"))
      (node (ref "SW6") (pin "13") (pinfunction "13_13") (pintype "passive"))
      (node (ref "SW6") (pin "14") (pinfunction "14_14") (pintype "passive"))
      (node (ref "SW6") (pin "15") (pinfunction "15_15") (pintype "passive"))
      (node (ref "SW6") (pin "16") (pinfunction "16_16") (pintype "passive"))
      (node (ref "SW6") (pin "9") (pinfunction "9_9") (pintype "passive"))
      (node (ref "SW7") (pin "10") (pinfunction "10_10") (pintype "passive"))
      (node (ref "SW7") (pin "11") (pinfunction "11_11") (pintype "passive"))
      (node (ref "SW7") (pin "12") (pinfunction "12_12") (pintype "passive"))
      (node (ref "SW7") (pin "13") (pinfunction "13_13") (pintype "passive"))
      (node (ref "SW7") (pin "14") (pinfunction "14_14") (pintype "passive"))
      (node (ref "SW7") (pin "15") (pinfunction "15_15") (pintype "passive"))
      (node (ref "SW7") (pin "16") (pinfunction "16_16") (pintype "passive"))
      (node (ref "SW7") (pin "9") (pinfunction "9_9") (pintype "passive"))
      (node (ref "SW8") (pin "10") (pinfunction "10_10") (pintype "passive"))
      (node (ref "SW8") (pin "11") (pinfunction "11_11") (pintype "passive"))
      (node (ref "SW8") (pin "12") (pinfunction "12_12") (pintype "passive"))
      (node (ref "SW8") (pin "13") (pinfunction "13_13") (pintype "passive"))
      (node (ref "SW8") (pin "14") (pinfunction "14_14") (pintype "passive"))
      (node (ref "SW8") (pin "15") (pinfunction "15_15") (pintype "passive"))
      (node (ref "SW8") (pin "16") (pinfunction "16_16") (pintype "passive"))
      (node (ref "SW8") (pin "9") (pinfunction "9_9") (pintype "passive"))
      (node (ref "T1") (pin "1") (pinfunction "E_1") (pintype "passive"))
      (node (ref "U1") (pin "10") (pinfunction "GND_10") (pintype "power_in"))
      (node (ref "U10") (pin "10") (pinfunction "GND_10") (pintype "power_in"))
      (node (ref "U10") (pin "12") (pinfunction "Q4_12") (pintype "input"))
      (node (ref "U10") (pin "14") (pinfunction "Q5_14") (pintype "input"))
      (node (ref "U10") (pin "16") (pinfunction "Q6_16") (pintype "input"))
      (node (ref "U10") (pin "18") (pinfunction "Q7_18") (pintype "input"))
      (node (ref "U10") (pin "3") (pinfunction "Q0_3") (pintype "input"))
      (node (ref "U10") (pin "5") (pinfunction "Q1_5") (pintype "input"))
      (node (ref "U10") (pin "9") (pinfunction "Q3_9") (pintype "input"))
      (node (ref "U11") (pin "7") (pinfunction "GND_7") (pintype "power_in"))
      (node (ref "U12") (pin "10") (pinfunction "I1_10") (pintype "input"))
      (node (ref "U12") (pin "4") (pinfunction "I0_4") (pintype "input"))
      (node (ref "U12") (pin "5") (pinfunction "I1_5") (pintype "input"))
      (node (ref "U12") (pin "7") (pinfunction "GND_7") (pintype "power_in"))
      (node (ref "U12") (pin "9") (pinfunction "I0_9") (pintype "input"))
      (node (ref "U13") (pin "7") (pinfunction "GND_7") (pintype "power_in"))
      (node (ref "U14") (pin "11") (pinfunction "I_11") (pintype "input"))
      (node (ref "U14") (pin "3") (pinfunction "I_3") (pintype "input"))
      (node (ref "U14") (pin "5") (pinfunction "I_5") (pintype "input"))
      (node (ref "U14") (pin "7") (pinfunction "GND_7") (pintype "power_in"))
      (node (ref "U14") (pin "9") (pinfunction "I_9") (pintype "input"))
      (node (ref "U15") (pin "10") (pinfunction "I1_10") (pintype "input"))
      (node (ref "U15") (pin "12") (pinfunction "I0_12") (pintype "input"))
      (node (ref "U15") (pin "13") (pinfunction "I1_13") (pintype "input"))
      (node (ref "U15") (pin "4") (pinfunction "I0_4") (pintype "input"))
      (node (ref "U15") (pin "5") (pinfunction "I1_5") (pintype "input"))
      (node (ref "U15") (pin "7") (pinfunction "GND_7") (pintype "power_in"))
      (node (ref "U15") (pin "9") (pinfunction "I0_9") (pintype "input"))
      (node (ref "U16") (pin "10") (pinfunction "GND_10") (pintype "power_in"))
      (node (ref "U16") (pin "12") (pinfunction "Q4_12") (pintype "input"))
      (node (ref "U16") (pin "14") (pinfunction "Q5_14") (pintype "input"))
      (node (ref "U16") (pin "16") (pinfunction "Q6_16") (pintype "input"))
      (node (ref "U16") (pin "18") (pinfunction "Q7_18") (pintype "input"))
      (node (ref "U16") (pin "2") (pinfunction "P0_2") (pintype "input"))
      (node (ref "U16") (pin "3") (pinfunction "Q0_3") (pintype "input"))
      (node (ref "U16") (pin "4") (pinfunction "P1_4") (pintype "input"))
      (node (ref "U16") (pin "5") (pinfunction "Q1_5") (pintype "input"))
      (node (ref "U16") (pin "6") (pinfunction "P2_6") (pintype "input"))
      (node (ref "U16") (pin "7") (pinfunction "Q2_7") (pintype "input"))
      (node (ref "U17") (pin "8") (pinfunction "GND_8") (pintype "power_in"))
      (node (ref "U18") (pin "8") (pinfunction "GND_8") (pintype "power_in"))
      (node (ref "U19") (pin "10") (pinfunction "GND_10") (pintype "power_in"))
      (node (ref "U2") (pin "10") (pinfunction "GND_10") (pintype "power_in"))
      (node (ref "U2") (pin "19") (pinfunction "G_19") (pintype "input"))
      (node (ref "U20") (pin "10") (pinfunction "GND_10") (pintype "power_in"))
      (node (ref "U21") (pin "10") (pinfunction "GND_10") (pintype "power_in"))
      (node (ref "U22") (pin "10") (pinfunction "GND_10") (pintype "power_in"))
      (node (ref "U23") (pin "1") (pinfunction "OC_1") (pintype "input"))
      (node (ref "U23") (pin "10") (pinfunction "GND_10") (pintype "power_in"))
      (node (ref "U24") (pin "1") (pinfunction "GND_1") (pintype "power_in"))
      (node (ref "U3") (pin "10") (pinfunction "GND_10") (pintype "power_in"))
      (node (ref "U3") (pin "19") (pinfunction "G_19") (pintype "input"))
      (node (ref "U3") (pin "7") (pinfunction "A6_7") (pintype "bidirectional"))
      (node (ref "U3") (pin "8") (pinfunction "A7_8") (pintype "bidirectional"))
      (node (ref "U4") (pin "10") (pinfunction "GND_10") (pintype "power_in"))
      (node (ref "U4") (pin "12") (pinfunction "Q4_12") (pintype "input"))
      (node (ref "U4") (pin "14") (pinfunction "Q5_14") (pintype "input"))
      (node (ref "U4") (pin "16") (pinfunction "Q6_16") (pintype "input"))
      (node (ref "U4") (pin "18") (pinfunction "Q7_18") (pintype "input"))
      (node (ref "U4") (pin "2") (pinfunction "P0_2") (pintype "input"))
      (node (ref "U4") (pin "3") (pinfunction "Q0_3") (pintype "input"))
      (node (ref "U4") (pin "4") (pinfunction "P1_4") (pintype "input"))
      (node (ref "U4") (pin "5") (pinfunction "Q1_5") (pintype "input"))
      (node (ref "U4") (pin "7") (pinfunction "Q2_7") (pintype "input"))
      (node (ref "U4") (pin "9") (pinfunction "Q3_9") (pintype "input"))
      (node (ref "U5") (pin "5") (pinfunction "GND_5") (pintype "power_in"))
      (node (ref "U6") (pin "7") (pinfunction "GND_7") (pintype "power_in"))
      (node (ref "U7") (pin "12") (pinfunction "CCKEN_12") (pintype "input"))
      (node (ref "U7") (pin "13") (pinfunction "RCK_13") (pintype "input"))
      (node (ref "U7") (pin "14") (pinfunction "G_14") (pintype "input"))
      (node (ref "U7") (pin "8") (pinfunction "GND_8") (pintype "power_in"))
      (node (ref "U8") (pin "10") (pinfunction "GND_10") (pintype "power_in"))
      (node (ref "U8") (pin "14") (pinfunction "Q5_14") (pintype "input"))
      (node (ref "U8") (pin "16") (pinfunction "Q6_16") (pintype "input"))
      (node (ref "U8") (pin "18") (pinfunction "Q7_18") (pintype "input"))
      (node (ref "U8") (pin "2") (pinfunction "P0_2") (pintype "input"))
      (node (ref "U8") (pin "3") (pinfunction "Q0_3") (pintype "input"))
      (node (ref "U8") (pin "4") (pinfunction "P1_4") (pintype "input"))
      (node (ref "U8") (pin "5") (pinfunction "Q1_5") (pintype "input"))
      (node (ref "U8") (pin "6") (pinfunction "P2_6") (pintype "input"))
      (node (ref "U8") (pin "7") (pinfunction "Q2_7") (pintype "input"))
      (node (ref "U8") (pin "8") (pinfunction "P3_8") (pintype "input"))
      (node (ref "U8") (pin "9") (pinfunction "Q3_9") (pintype "input"))
      (node (ref "U9") (pin "14") (pinfunction "GND_14") (pintype "power_in"))
      (node (ref "U9") (pin "20") (pinfunction "GND1_20") (pintype "power_in"))
      (node (ref "Y1") (pin "7") (pinfunction "GND_7") (pintype "power_in"))
    )
    (net (code "62") (name "Net-(BUSAA-S)") (class "Default")
      (node (ref "BUS") (pin "33") (pinfunction "S_33") (pintype "passive"))
      (node (ref "U2") (pin "9") (pinfunction "A8_9") (pintype "bidirectional"))
    )
    (net (code "63") (name "Net-(BUSAB-S)") (class "Default")
      (node (ref "BUS") (pin "34") (pinfunction "S_34") (pintype "passive"))
      (node (ref "U2") (pin "8") (pinfunction "A7_8") (pintype "bidirectional"))
    )
    (net (code "64") (name "Net-(BUSAC-S)") (class "Default")
      (node (ref "BUS") (pin "35") (pinfunction "S_35") (pintype "passive"))
      (node (ref "U2") (pin "7") (pinfunction "A6_7") (pintype "bidirectional"))
    )
    (net (code "65") (name "Net-(BUSAD-S)") (class "Default")
      (node (ref "BUS") (pin "36") (pinfunction "S_36") (pintype "passive"))
      (node (ref "U2") (pin "6") (pinfunction "A5_6") (pintype "bidirectional"))
    )
    (net (code "66") (name "Net-(BUSAE-S)") (class "Default")
      (node (ref "BUS") (pin "37") (pinfunction "S_37") (pintype "passive"))
      (node (ref "U2") (pin "5") (pinfunction "A4_5") (pintype "bidirectional"))
    )
    (net (code "67") (name "Net-(BUSAF-S)") (class "Default")
      (node (ref "BUS") (pin "38") (pinfunction "S_38") (pintype "passive"))
      (node (ref "U2") (pin "4") (pinfunction "A3_4") (pintype "bidirectional"))
    )
    (net (code "68") (name "Net-(BUSAG-S)") (class "Default")
      (node (ref "BUS") (pin "39") (pinfunction "S_39") (pintype "passive"))
      (node (ref "U2") (pin "3") (pinfunction "A2_3") (pintype "bidirectional"))
    )
    (net (code "69") (name "Net-(BUSAI-S)") (class "Default")
      (node (ref "BUS") (pin "40") (pinfunction "S_40") (pintype "passive"))
      (node (ref "U2") (pin "2") (pinfunction "A1_2") (pintype "bidirectional"))
    )
    (net (code "70") (name "Net-(BUSAJ-S)") (class "Default")
      (node (ref "BUS") (pin "5") (pinfunction "S_5") (pintype "passive"))
      (node (ref "U3") (pin "9") (pinfunction "A8_9") (pintype "bidirectional"))
    )
    (net (code "71") (name "Net-(BUSAL-S)") (class "Default")
      (node (ref "BUS") (pin "7") (pinfunction "S_7") (pintype "passive"))
      (node (ref "U3") (pin "6") (pinfunction "A5_6") (pintype "bidirectional"))
    )
    (net (code "72") (name "Net-(BUSAM-S)") (class "Default")
      (node (ref "BUS") (pin "8") (pinfunction "S_8") (pintype "passive"))
      (node (ref "U3") (pin "5") (pinfunction "A4_5") (pintype "bidirectional"))
    )
    (net (code "73") (name "Net-(BUSAN-S)") (class "Default")
      (node (ref "BUS") (pin "9") (pinfunction "S_9") (pintype "passive"))
      (node (ref "U3") (pin "4") (pinfunction "A3_4") (pintype "bidirectional"))
    )
    (net (code "74") (name "Net-(BUSE-S)") (class "Default")
      (node (ref "BUS") (pin "13") (pinfunction "S_13") (pintype "passive"))
      (node (ref "U3") (pin "3") (pinfunction "A2_3") (pintype "bidirectional"))
    )
    (net (code "75") (name "Net-(BUSF-S)") (class "Default")
      (node (ref "BUS") (pin "14") (pinfunction "S_14") (pintype "passive"))
      (node (ref "U3") (pin "2") (pinfunction "A1_2") (pintype "bidirectional"))
    )
    (net (code "76") (name "Net-(BUSP-S)") (class "Default")
      (node (ref "BUS") (pin "23") (pinfunction "S_23") (pintype "passive"))
      (node (ref "U1") (pin "9") (pinfunction "A8_9") (pintype "bidirectional"))
    )
    (net (code "77") (name "Net-(BUSQ-S)") (class "Default")
      (node (ref "BUS") (pin "24") (pinfunction "S_24") (pintype "passive"))
      (node (ref "U1") (pin "8") (pinfunction "A7_8") (pintype "bidirectional"))
    )
    (net (code "78") (name "Net-(BUSR-S)") (class "Default")
      (node (ref "BUS") (pin "25") (pinfunction "S_25") (pintype "passive"))
      (node (ref "U1") (pin "7") (pinfunction "A6_7") (pintype "bidirectional"))
    )
    (net (code "79") (name "Net-(BUSS-S)") (class "Default")
      (node (ref "BUS") (pin "26") (pinfunction "S_26") (pintype "passive"))
      (node (ref "U1") (pin "6") (pinfunction "A5_6") (pintype "bidirectional"))
    )
    (net (code "80") (name "Net-(BUST-S)") (class "Default")
      (node (ref "BUS") (pin "27") (pinfunction "S_27") (pintype "passive"))
      (node (ref "U1") (pin "5") (pinfunction "A4_5") (pintype "bidirectional"))
    )
    (net (code "81") (name "Net-(BUSU-S)") (class "Default")
      (node (ref "BUS") (pin "28") (pinfunction "S_28") (pintype "passive"))
      (node (ref "U1") (pin "4") (pinfunction "A3_4") (pintype "bidirectional"))
    )
    (net (code "82") (name "Net-(BUSV-S)") (class "Default")
      (node (ref "BUS") (pin "29") (pinfunction "S_29") (pintype "passive"))
      (node (ref "U1") (pin "3") (pinfunction "A2_3") (pintype "bidirectional"))
    )
    (net (code "83") (name "Net-(BUSX-S)") (class "Default")
      (node (ref "BUS") (pin "30") (pinfunction "S_30") (pintype "passive"))
      (node (ref "U1") (pin "2") (pinfunction "A1_2") (pintype "bidirectional"))
    )
    (net (code "84") (name "Net-(RN2A-1)") (class "Default")
      (node (ref "RN2") (pin "2") (pinfunction "1_2") (pintype "passive"))
      (node (ref "U5") (pin "23") (pinfunction "TRG0_23") (pintype "input"))
    )
    (net (code "85") (name "Net-(RN2B-1)") (class "Default")
      (node (ref "RN2") (pin "3") (pinfunction "1_3") (pintype "passive"))
      (node (ref "U5") (pin "22") (pinfunction "TRG1_22") (pintype "input"))
      (node (ref "U7") (pin "9") (pinfunction "RCO_9") (pintype "output"))
    )
    (net (code "86") (name "Net-(RN2C-1)") (class "Default")
      (node (ref "RN2") (pin "4") (pinfunction "1_4") (pintype "passive"))
      (node (ref "U5") (pin "21") (pinfunction "TRG2_21") (pintype "input"))
    )
    (net (code "87") (name "Net-(RN2D-1)") (class "Default")
      (node (ref "RN2") (pin "5") (pinfunction "1_5") (pintype "passive"))
      (node (ref "U5") (pin "20") (pinfunction "TRG3_20") (pintype "input"))
      (node (ref "U9") (pin "5") (pinfunction "~{INT}_5") (pintype "open_collector"))
    )
    (net (code "88") (name "Net-(RN3A-1)") (class "Default")
      (node (ref "RN3") (pin "2") (pinfunction "1_2") (pintype "passive"))
      (node (ref "SW1") (pin "1") (pinfunction "S_1") (pintype "passive"))
      (node (ref "SW1") (pin "2") (pinfunction "S1_2") (pintype "passive"))
      (node (ref "U19") (pin "2") (pinfunction "1D_2") (pintype "input"))
    )
    (net (code "89") (name "Net-(RN3B-1)") (class "Default")
      (node (ref "RN3") (pin "3") (pinfunction "1_3") (pintype "passive"))
      (node (ref "SW2") (pin "1") (pinfunction "S_1") (pintype "passive"))
      (node (ref "SW2") (pin "2") (pinfunction "S1_2") (pintype "passive"))
      (node (ref "U19") (pin "3") (pinfunction "2D_3") (pintype "input"))
    )
    (net (code "90") (name "Net-(RN3C-1)") (class "Default")
      (node (ref "RN3") (pin "4") (pinfunction "1_4") (pintype "passive"))
      (node (ref "SW3") (pin "1") (pinfunction "S_1") (pintype "passive"))
      (node (ref "SW3") (pin "2") (pinfunction "S1_2") (pintype "passive"))
      (node (ref "U19") (pin "4") (pinfunction "3D_4") (pintype "input"))
    )
    (net (code "91") (name "Net-(RN3D-1)") (class "Default")
      (node (ref "RN3") (pin "5") (pinfunction "1_5") (pintype "passive"))
      (node (ref "SW4") (pin "1") (pinfunction "S_1") (pintype "passive"))
      (node (ref "SW4") (pin "2") (pinfunction "S1_2") (pintype "passive"))
      (node (ref "U19") (pin "5") (pinfunction "4D_5") (pintype "input"))
    )
    (net (code "92") (name "Net-(RN3E-1)") (class "Default")
      (node (ref "RN3") (pin "6") (pinfunction "1_6") (pintype "passive"))
      (node (ref "SW5") (pin "1") (pinfunction "1_1") (pintype "passive"))
      (node (ref "U19") (pin "6") (pinfunction "5D_6") (pintype "input"))
    )
    (net (code "93") (name "Net-(RN3F-1)") (class "Default")
      (node (ref "RN3") (pin "7") (pinfunction "1_7") (pintype "passive"))
      (node (ref "SW5") (pin "2") (pinfunction "2_2") (pintype "passive"))
      (node (ref "U19") (pin "7") (pinfunction "6D_7") (pintype "input"))
    )
    (net (code "94") (name "Net-(RN3G-1)") (class "Default")
      (node (ref "RN3") (pin "8") (pinfunction "1_8") (pintype "passive"))
      (node (ref "SW5") (pin "3") (pinfunction "3_3") (pintype "passive"))
      (node (ref "U19") (pin "8") (pinfunction "7D_8") (pintype "input"))
    )
    (net (code "95") (name "Net-(RN3H-1)") (class "Default")
      (node (ref "RN3") (pin "9") (pinfunction "1_9") (pintype "passive"))
      (node (ref "SW5") (pin "4") (pinfunction "4_4") (pintype "passive"))
      (node (ref "U19") (pin "9") (pinfunction "8D_9") (pintype "input"))
    )
    (net (code "96") (name "Net-(RN4A-1)") (class "Default")
      (node (ref "RN4") (pin "2") (pinfunction "1_2") (pintype "passive"))
      (node (ref "SW6") (pin "1") (pinfunction "1_1") (pintype "passive"))
      (node (ref "U20") (pin "2") (pinfunction "1D_2") (pintype "input"))
    )
    (net (code "97") (name "Net-(RN4B-1)") (class "Default")
      (node (ref "RN4") (pin "3") (pinfunction "1_3") (pintype "passive"))
      (node (ref "SW6") (pin "2") (pinfunction "2_2") (pintype "passive"))
      (node (ref "U20") (pin "3") (pinfunction "2D_3") (pintype "input"))
    )
    (net (code "98") (name "Net-(RN4C-1)") (class "Default")
      (node (ref "RN4") (pin "4") (pinfunction "1_4") (pintype "passive"))
      (node (ref "SW6") (pin "3") (pinfunction "3_3") (pintype "passive"))
      (node (ref "U20") (pin "4") (pinfunction "3D_4") (pintype "input"))
    )
    (net (code "99") (name "Net-(RN4D-1)") (class "Default")
      (node (ref "RN4") (pin "5") (pinfunction "1_5") (pintype "passive"))
      (node (ref "SW6") (pin "4") (pinfunction "4_4") (pintype "passive"))
      (node (ref "U20") (pin "5") (pinfunction "4D_5") (pintype "input"))
    )
    (net (code "100") (name "Net-(RN4E-1)") (class "Default")
      (node (ref "RN4") (pin "6") (pinfunction "1_6") (pintype "passive"))
      (node (ref "SW6") (pin "5") (pinfunction "5_5") (pintype "passive"))
      (node (ref "U20") (pin "6") (pinfunction "5D_6") (pintype "input"))
    )
    (net (code "101") (name "Net-(RN4F-1)") (class "Default")
      (node (ref "RN4") (pin "7") (pinfunction "1_7") (pintype "passive"))
      (node (ref "SW6") (pin "6") (pinfunction "6_6") (pintype "passive"))
      (node (ref "U20") (pin "7") (pinfunction "6D_7") (pintype "input"))
    )
    (net (code "102") (name "Net-(RN4G-1)") (class "Default")
      (node (ref "RN4") (pin "8") (pinfunction "1_8") (pintype "passive"))
      (node (ref "SW6") (pin "7") (pinfunction "7_7") (pintype "passive"))
      (node (ref "U20") (pin "8") (pinfunction "7D_8") (pintype "input"))
    )
    (net (code "103") (name "Net-(RN4H-1)") (class "Default")
      (node (ref "RN4") (pin "9") (pinfunction "1_9") (pintype "passive"))
      (node (ref "SW6") (pin "8") (pinfunction "8_8") (pintype "passive"))
      (node (ref "U20") (pin "9") (pinfunction "8D_9") (pintype "input"))
    )
    (net (code "104") (name "Net-(RN5A-1)") (class "Default")
      (node (ref "RN5") (pin "2") (pinfunction "1_2") (pintype "passive"))
      (node (ref "SW7") (pin "1") (pinfunction "1_1") (pintype "passive"))
      (node (ref "U21") (pin "2") (pinfunction "1D_2") (pintype "input"))
    )
    (net (code "105") (name "Net-(RN5B-1)") (class "Default")
      (node (ref "RN5") (pin "3") (pinfunction "1_3") (pintype "passive"))
      (node (ref "SW7") (pin "2") (pinfunction "2_2") (pintype "passive"))
      (node (ref "U21") (pin "3") (pinfunction "2D_3") (pintype "input"))
    )
    (net (code "106") (name "Net-(RN5C-1)") (class "Default")
      (node (ref "RN5") (pin "4") (pinfunction "1_4") (pintype "passive"))
      (node (ref "SW7") (pin "3") (pinfunction "3_3") (pintype "passive"))
      (node (ref "U21") (pin "4") (pinfunction "3D_4") (pintype "input"))
    )
    (net (code "107") (name "Net-(RN5D-1)") (class "Default")
      (node (ref "RN5") (pin "5") (pinfunction "1_5") (pintype "passive"))
      (node (ref "SW7") (pin "4") (pinfunction "4_4") (pintype "passive"))
      (node (ref "U21") (pin "5") (pinfunction "4D_5") (pintype "input"))
    )
    (net (code "108") (name "Net-(RN5E-1)") (class "Default")
      (node (ref "RN5") (pin "6") (pinfunction "1_6") (pintype "passive"))
      (node (ref "SW7") (pin "5") (pinfunction "5_5") (pintype "passive"))
      (node (ref "U21") (pin "6") (pinfunction "5D_6") (pintype "input"))
    )
    (net (code "109") (name "Net-(RN5F-1)") (class "Default")
      (node (ref "RN5") (pin "7") (pinfunction "1_7") (pintype "passive"))
      (node (ref "SW7") (pin "6") (pinfunction "6_6") (pintype "passive"))
      (node (ref "U21") (pin "7") (pinfunction "6D_7") (pintype "input"))
    )
    (net (code "110") (name "Net-(RN5G-1)") (class "Default")
      (node (ref "RN5") (pin "8") (pinfunction "1_8") (pintype "passive"))
      (node (ref "SW7") (pin "7") (pinfunction "7_7") (pintype "passive"))
      (node (ref "U21") (pin "8") (pinfunction "7D_8") (pintype "input"))
    )
    (net (code "111") (name "Net-(RN5H-1)") (class "Default")
      (node (ref "RN5") (pin "9") (pinfunction "1_9") (pintype "passive"))
      (node (ref "SW7") (pin "8") (pinfunction "8_8") (pintype "passive"))
      (node (ref "U21") (pin "9") (pinfunction "8D_9") (pintype "input"))
    )
    (net (code "112") (name "Net-(RN6A-1)") (class "Default")
      (node (ref "RN6") (pin "2") (pinfunction "1_2") (pintype "passive"))
      (node (ref "SW8") (pin "1") (pinfunction "1_1") (pintype "passive"))
      (node (ref "U22") (pin "2") (pinfunction "1D_2") (pintype "input"))
    )
    (net (code "113") (name "Net-(RN6B-1)") (class "Default")
      (node (ref "RN6") (pin "3") (pinfunction "1_3") (pintype "passive"))
      (node (ref "SW8") (pin "2") (pinfunction "2_2") (pintype "passive"))
      (node (ref "U22") (pin "3") (pinfunction "2D_3") (pintype "input"))
    )
    (net (code "114") (name "Net-(RN6C-1)") (class "Default")
      (node (ref "RN6") (pin "4") (pinfunction "1_4") (pintype "passive"))
      (node (ref "SW8") (pin "3") (pinfunction "3_3") (pintype "passive"))
      (node (ref "U22") (pin "4") (pinfunction "3D_4") (pintype "input"))
    )
    (net (code "115") (name "Net-(RN6D-1)") (class "Default")
      (node (ref "RN6") (pin "5") (pinfunction "1_5") (pintype "passive"))
      (node (ref "SW8") (pin "4") (pinfunction "4_4") (pintype "passive"))
      (node (ref "U22") (pin "5") (pinfunction "4D_5") (pintype "input"))
    )
    (net (code "116") (name "Net-(RN6E-1)") (class "Default")
      (node (ref "RN6") (pin "6") (pinfunction "1_6") (pintype "passive"))
      (node (ref "SW8") (pin "5") (pinfunction "5_5") (pintype "passive"))
      (node (ref "U22") (pin "6") (pinfunction "5D_6") (pintype "input"))
    )
    (net (code "117") (name "Net-(RN6F-1)") (class "Default")
      (node (ref "RN6") (pin "7") (pinfunction "1_7") (pintype "passive"))
      (node (ref "SW8") (pin "6") (pinfunction "6_6") (pintype "passive"))
      (node (ref "U22") (pin "7") (pinfunction "6D_7") (pintype "input"))
    )
    (net (code "118") (name "Net-(RN6G-1)") (class "Default")
      (node (ref "RN6") (pin "8") (pinfunction "1_8") (pintype "passive"))
      (node (ref "SW8") (pin "7") (pinfunction "7_7") (pintype "passive"))
      (node (ref "U22") (pin "8") (pinfunction "7D_8") (pintype "input"))
    )
    (net (code "119") (name "Net-(RN6H-1)") (class "Default")
      (node (ref "RN6") (pin "9") (pinfunction "1_9") (pintype "passive"))
      (node (ref "SW8") (pin "8") (pinfunction "8_8") (pintype "passive"))
      (node (ref "U22") (pin "9") (pinfunction "8D_9") (pintype "input"))
    )
    (net (code "120") (name "Net-(SG1-2)") (class "Default")
      (node (ref "R1") (pin "1") (pinfunction "1_1") (pintype "passive"))
      (node (ref "SG1") (pin "-") (pinfunction "2_-") (pintype "passive"))
      (node (ref "U24") (pin "3") (pinfunction "OUT_3") (pintype "output"))
    )
    (net (code "121") (name "Net-(T1-B)") (class "Default")
      (node (ref "R2") (pin "2") (pinfunction "2_2") (pintype "passive"))
      (node (ref "T1") (pin "2") (pinfunction "B_2") (pintype "passive"))
    )
    (net (code "122") (name "Net-(U6A-CLK)") (class "Default")
      (node (ref "JP1") (pin "1") (pinfunction "1_1") (pintype "passive"))
      (node (ref "U6") (pin "3") (pinfunction "CLK_3") (pintype "input"))
      (node (ref "Y1") (pin "8") (pinfunction "OUT_8") (pintype "output"))
    )
    (net (code "123") (name "Net-(U6A-D)") (class "Default")
      (node (ref "JP1") (pin "3") (pinfunction "3_3") (pintype "passive"))
      (node (ref "U6") (pin "11") (pinfunction "CLK_11") (pintype "input"))
      (node (ref "U6") (pin "2") (pinfunction "D_2") (pintype "input"))
      (node (ref "U6") (pin "6") (pinfunction "~{Q}_6") (pintype "output"))
    )
    (net (code "124") (name "Net-(U6B-D)") (class "Default")
      (node (ref "JP1") (pin "5") (pinfunction "5_5") (pintype "passive"))
      (node (ref "U6") (pin "12") (pinfunction "D_12") (pintype "input"))
      (node (ref "U6") (pin "8") (pinfunction "~{Q}_8") (pintype "output"))
    )
    (net (code "125") (name "Net-(U7A-CLK)") (class "Default")
      (node (ref "JP1") (pin "2") (pinfunction "2_2") (pintype "passive"))
      (node (ref "JP1") (pin "4") (pinfunction "4_4") (pintype "passive"))
      (node (ref "JP1") (pin "6") (pinfunction "6_6") (pintype "passive"))
      (node (ref "U7") (pin "11") (pinfunction "CLK_11") (pintype "input"))
    )
    (net (code "126") (name "Net-(U9-BC)") (class "Default")
      (node (ref "BAT1") (pin "+") (pinfunction "+_+") (pintype "passive"))
      (node (ref "U9") (pin "24") (pinfunction "BC_24") (pintype "power_in"))
    )
    (net (code "127") (name "Net-(U9-X1)") (class "Default")
      (node (ref "U9") (pin "2") (pinfunction "X1_2") (pintype "input"))
      (node (ref "X1") (pin "1") (pinfunction "1_1") (pintype "passive"))
    )
    (net (code "128") (name "Net-(U9-X2)") (class "Default")
      (node (ref "U9") (pin "3") (pinfunction "X2_3") (pintype "input"))
      (node (ref "X1") (pin "2") (pinfunction "2_2") (pintype "passive"))
    )
    (net (code "129") (name "Net-(U9-~{RST})") (class "Default")
      (node (ref "JP2") (pin "2") (pinfunction "2_2") (pintype "passive"))
      (node (ref "U9") (pin "6") (pinfunction "~{RST}_6") (pintype "open_collector"))
    )
    (net (code "130") (name "Net-(U10A-P=Q)") (class "Default")
      (node (ref "U10") (pin "19") (pinfunction "P=Q_19") (pintype "output"))
      (node (ref "U11") (pin "2") (pinfunction "I1_2") (pintype "input"))
      (node (ref "U9") (pin "23") (pinfunction "WDI_23") (pintype "input"))
    )
    (net (code "131") (name "Net-(U11A-I0)") (class "Default")
      (node (ref "U11") (pin "1") (pinfunction "I0_1") (pintype "input"))
      (node (ref "U8") (pin "19") (pinfunction "P=Q_19") (pintype "output"))
      (node (ref "U9") (pin "21") (pinfunction "~{CS}_21") (pintype "input"))
    )
    (net (code "132") (name "Net-(U11A-I2)") (class "Default")
      (node (ref "U11") (pin "3") (pinfunction "I2_3") (pintype "input"))
      (node (ref "U4") (pin "19") (pinfunction "P=Q_19") (pintype "output"))
      (node (ref "U5") (pin "16") (pinfunction "CE_16") (pintype "input"))
    )
    (net (code "133") (name "Net-(U11A-I3)") (class "Default")
      (node (ref "U11") (pin "4") (pinfunction "I3_4") (pintype "input"))
      (node (ref "U17") (pin "15") (pinfunction "Y0_15") (pintype "output"))
      (node (ref "U19") (pin "1") (pinfunction "OC_1") (pintype "input"))
      (node (ref "U19") (pin "11") (pinfunction "C_11") (pintype "input"))
    )
    (net (code "134") (name "Net-(U11A-I4)") (class "Default")
      (node (ref "U11") (pin "5") (pinfunction "I4_5") (pintype "input"))
      (node (ref "U17") (pin "14") (pinfunction "Y1_14") (pintype "output"))
      (node (ref "U20") (pin "1") (pinfunction "OC_1") (pintype "input"))
      (node (ref "U20") (pin "11") (pinfunction "C_11") (pintype "input"))
    )
    (net (code "135") (name "Net-(U11A-I5)") (class "Default")
      (node (ref "U11") (pin "6") (pinfunction "I5_6") (pintype "input"))
      (node (ref "U17") (pin "13") (pinfunction "Y2_13") (pintype "output"))
      (node (ref "U22") (pin "1") (pinfunction "OC_1") (pintype "input"))
      (node (ref "U22") (pin "11") (pinfunction "C_11") (pintype "input"))
    )
    (net (code "136") (name "Net-(U11A-I6)") (class "Default")
      (node (ref "U11") (pin "11") (pinfunction "I6_11") (pintype "input"))
      (node (ref "U17") (pin "12") (pinfunction "Y3_12") (pintype "output"))
      (node (ref "U21") (pin "1") (pinfunction "OC_1") (pintype "input"))
      (node (ref "U21") (pin "11") (pinfunction "C_11") (pintype "input"))
    )
    (net (code "137") (name "Net-(U11A-I7)") (class "Default")
      (node (ref "U11") (pin "12") (pinfunction "I7_12") (pintype "input"))
      (node (ref "U12") (pin "12") (pinfunction "I0_12") (pintype "input"))
      (node (ref "U18") (pin "11") (pinfunction "Y4_11") (pintype "output"))
    )
    (net (code "138") (name "Net-(U11A-O)") (class "Default")
      (node (ref "U11") (pin "8") (pinfunction "O_8") (pintype "output"))
      (node (ref "U12") (pin "1") (pinfunction "I0_1") (pintype "input"))
    )
    (net (code "139") (name "Net-(U12A-I1)") (class "Default")
      (node (ref "U12") (pin "2") (pinfunction "I1_2") (pintype "input"))
      (node (ref "U14") (pin "12") (pinfunction "O_12") (pintype "output"))
    )
    (net (code "140") (name "Net-(U12A-O)") (class "Default")
      (node (ref "U12") (pin "3") (pinfunction "O_3") (pintype "output"))
      (node (ref "U15") (pin "1") (pinfunction "I0_1") (pintype "input"))
    )
    (net (code "141") (name "Net-(U12D-O)") (class "Default")
      (node (ref "U12") (pin "11") (pinfunction "O_11") (pintype "output"))
      (node (ref "U23") (pin "11") (pinfunction "C_11") (pintype "input"))
    )
    (net (code "142") (name "Net-(U13A-I1)") (class "Default")
      (node (ref "U13") (pin "2") (pinfunction "I1_2") (pintype "input"))
      (node (ref "U13") (pin "8") (pinfunction "O_8") (pintype "output"))
    )
    (net (code "143") (name "Net-(U13A-O)") (class "Default")
      (node (ref "U13") (pin "3") (pinfunction "O_3") (pintype "output"))
      (node (ref "U15") (pin "2") (pinfunction "I1_2") (pintype "input"))
    )
    (net (code "144") (name "Net-(U13B-O)") (class "Default")
      (node (ref "U13") (pin "6") (pinfunction "O_6") (pintype "output"))
      (node (ref "U17") (pin "5") (pinfunction "G2B_5") (pintype "input"))
    )
    (net (code "145") (name "Net-(U13D-O)") (class "Default")
      (node (ref "U13") (pin "11") (pinfunction "O_11") (pintype "output"))
      (node (ref "U18") (pin "5") (pinfunction "G2B_5") (pintype "input"))
    )
    (net (code "146") (name "Net-(U14A-O)") (class "Default")
      (node (ref "U1") (pin "19") (pinfunction "G_19") (pintype "input"))
      (node (ref "U14") (pin "2") (pinfunction "O_2") (pintype "output"))
    )
    (net (code "147") (name "Net-(U16A-P=Q)") (class "Default")
      (node (ref "U16") (pin "19") (pinfunction "P=Q_19") (pintype "output"))
      (node (ref "U17") (pin "4") (pinfunction "G2A_4") (pintype "input"))
      (node (ref "U18") (pin "4") (pinfunction "G2A_4") (pintype "input"))
    )
    (net (code "148") (name "Net-(U23A-8Q)") (class "Default")
      (node (ref "U23") (pin "12") (pinfunction "8Q_12") (pintype "tri_state"))
      (node (ref "U24") (pin "4") (pinfunction "/RES_4") (pintype "input"))
    )
    (net (code "149") (name "Net-(U24-CON)") (class "Default")
      (node (ref "C27") (pin "1") (pinfunction "1_1") (pintype "passive"))
      (node (ref "U24") (pin "5") (pinfunction "CON_5") (pintype "input"))
    )
    (net (code "150") (name "Net-(U24-DIS)") (class "Default")
      (node (ref "R4") (pin "1") (pinfunction "1_1") (pintype "passive"))
      (node (ref "R5") (pin "2") (pinfunction "2_2") (pintype "passive"))
      (node (ref "U24") (pin "7") (pinfunction "DIS_7") (pintype "input"))
    )
    (net (code "151") (name "Net-(U24-TRE)") (class "Default")
      (node (ref "C28") (pin "1") (pinfunction "1_1") (pintype "passive"))
      (node (ref "R5") (pin "1") (pinfunction "1_1") (pintype "passive"))
      (node (ref "U24") (pin "2") (pinfunction "TRI_2") (pintype "input"))
      (node (ref "U24") (pin "6") (pinfunction "TRE_6") (pintype "input"))
    )
    (net (code "152") (name "unconnected-(BAT1-+-Pad+@1)") (class "Default")
      (node (ref "BAT1") (pin "+@1") (pinfunction "+_+@1") (pintype "passive"))
    )
    (net (code "153") (name "unconnected-(BUSH-S-Pad16)") (class "Default")
      (node (ref "BUS") (pin "16") (pinfunction "S_16") (pintype "passive"))
    )
    (net (code "154") (name "unconnected-(BUSI-S-Pad17)") (class "Default")
      (node (ref "BUS") (pin "17") (pinfunction "S_17") (pintype "passive"))
    )
    (net (code "155") (name "unconnected-(BUSJ-S-Pad18)") (class "Default")
      (node (ref "BUS") (pin "18") (pinfunction "S_18") (pintype "passive"))
    )
    (net (code "156") (name "unconnected-(BUSK-S-Pad19)") (class "Default")
      (node (ref "BUS") (pin "19") (pinfunction "S_19") (pintype "passive"))
    )
    (net (code "157") (name "unconnected-(BUSM-S-Pad20)") (class "Default")
      (node (ref "BUS") (pin "20") (pinfunction "S_20") (pintype "passive"))
    )
    (net (code "158") (name "unconnected-(BUSN-S-Pad21)") (class "Default")
      (node (ref "BUS") (pin "21") (pinfunction "S_21") (pintype "passive"))
    )
    (net (code "159") (name "unconnected-(BUSO-S-Pad22)") (class "Default")
      (node (ref "BUS") (pin "22") (pinfunction "S_22") (pintype "passive"))
    )
    (net (code "160") (name "unconnected-(BUSY-S-Pad31)") (class "Default")
      (node (ref "BUS") (pin "31") (pinfunction "S_31") (pintype "passive"))
    )
    (net (code "161") (name "unconnected-(BUSZ-S-Pad32)") (class "Default")
      (node (ref "BUS") (pin "32") (pinfunction "S_32") (pintype "passive"))
    )
    (net (code "162") (name "unconnected-(R2-Pad1)") (class "Default")
      (node (ref "R2") (pin "1") (pinfunction "1_1") (pintype "passive"))
    )
    (net (code "163") (name "unconnected-(T1-C-Pad3)") (class "Default")
      (node (ref "T1") (pin "3") (pinfunction "C_3") (pintype "passive"))
    )
    (net (code "164") (name "unconnected-(U3A-B6-Pad13)") (class "Default")
      (node (ref "U3") (pin "13") (pinfunction "B6_13") (pintype "bidirectional"))
    )
    (net (code "165") (name "unconnected-(U3A-B7-Pad12)") (class "Default")
      (node (ref "U3") (pin "12") (pinfunction "B7_12") (pintype "bidirectional"))
    )
    (net (code "166") (name "unconnected-(U5-TO0-Pad7)") (class "Default")
      (node (ref "U5") (pin "7") (pinfunction "TO0_7") (pintype "output"))
    )
    (net (code "167") (name "unconnected-(U5-TO1-Pad8)") (class "Default")
      (node (ref "U5") (pin "8") (pinfunction "TO1_8") (pintype "output"))
    )
    (net (code "168") (name "unconnected-(U5-TO2-Pad9)") (class "Default")
      (node (ref "U5") (pin "9") (pinfunction "TO2_9") (pintype "output"))
    )
    (net (code "169") (name "unconnected-(U6A-Q-Pad5)") (class "Default")
      (node (ref "U6") (pin "5") (pinfunction "Q_5") (pintype "output"))
    )
    (net (code "170") (name "unconnected-(U6B-Q-Pad9)") (class "Default")
      (node (ref "U6") (pin "9") (pinfunction "Q_9") (pintype "output"))
    )
    (net (code "171") (name "unconnected-(U7A-QA-Pad15)") (class "Default")
      (node (ref "U7") (pin "15") (pinfunction "QA_15") (pintype "tri_state"))
    )
    (net (code "172") (name "unconnected-(U7A-QB-Pad1)") (class "Default")
      (node (ref "U7") (pin "1") (pinfunction "QB_1") (pintype "tri_state"))
    )
    (net (code "173") (name "unconnected-(U7A-QC-Pad2)") (class "Default")
      (node (ref "U7") (pin "2") (pinfunction "QC_2") (pintype "tri_state"))
    )
    (net (code "174") (name "unconnected-(U7A-QD-Pad3)") (class "Default")
      (node (ref "U7") (pin "3") (pinfunction "QD_3") (pintype "tri_state"))
    )
    (net (code "175") (name "unconnected-(U7A-QE-Pad4)") (class "Default")
      (node (ref "U7") (pin "4") (pinfunction "QE_4") (pintype "tri_state"))
    )
    (net (code "176") (name "unconnected-(U7A-QF-Pad5)") (class "Default")
      (node (ref "U7") (pin "5") (pinfunction "QF_5") (pintype "tri_state"))
    )
    (net (code "177") (name "unconnected-(U7A-QG-Pad6)") (class "Default")
      (node (ref "U7") (pin "6") (pinfunction "QG_6") (pintype "tri_state"))
    )
    (net (code "178") (name "unconnected-(U7A-QH-Pad7)") (class "Default")
      (node (ref "U7") (pin "7") (pinfunction "QH_7") (pintype "tri_state"))
    )
    (net (code "179") (name "unconnected-(U9-V_OUT-Pad1)") (class "Default")
      (node (ref "U9") (pin "1") (pinfunction "V_OUT_1") (pintype "bidirectional"))
    )
    (net (code "180") (name "unconnected-(U9-~{CE_OUT}-Pad25)") (class "Default")
      (node (ref "U9") (pin "25") (pinfunction "~{CE_OUT}_25") (pintype "bidirectional"))
    )
    (net (code "181") (name "unconnected-(U9-~{WDO}-Pad4)") (class "Default")
      (node (ref "U9") (pin "4") (pinfunction "~{WDO}_4") (pintype "output"))
    )
    (net (code "182") (name "unconnected-(U12B-O-Pad6)") (class "Default")
      (node (ref "U12") (pin "6") (pinfunction "O_6") (pintype "output"))
    )
    (net (code "183") (name "unconnected-(U12C-O-Pad8)") (class "Default")
      (node (ref "U12") (pin "8") (pinfunction "O_8") (pintype "output"))
    )
    (net (code "184") (name "unconnected-(U14B-O-Pad4)") (class "Default")
      (node (ref "U14") (pin "4") (pinfunction "O_4") (pintype "output"))
    )
    (net (code "185") (name "unconnected-(U14C-O-Pad6)") (class "Default")
      (node (ref "U14") (pin "6") (pinfunction "O_6") (pintype "output"))
    )
    (net (code "186") (name "unconnected-(U14D-O-Pad8)") (class "Default")
      (node (ref "U14") (pin "8") (pinfunction "O_8") (pintype "output"))
    )
    (net (code "187") (name "unconnected-(U14E-O-Pad10)") (class "Default")
      (node (ref "U14") (pin "10") (pinfunction "O_10") (pintype "output"))
    )
    (net (code "188") (name "unconnected-(U15B-O-Pad6)") (class "Default")
      (node (ref "U15") (pin "6") (pinfunction "O_6") (pintype "output"))
    )
    (net (code "189") (name "unconnected-(U15C-O-Pad8)") (class "Default")
      (node (ref "U15") (pin "8") (pinfunction "O_8") (pintype "output"))
    )
    (net (code "190") (name "unconnected-(U15D-O-Pad11)") (class "Default")
      (node (ref "U15") (pin "11") (pinfunction "O_11") (pintype "output"))
    )
    (net (code "191") (name "unconnected-(U17A-Y4-Pad11)") (class "Default")
      (node (ref "U17") (pin "11") (pinfunction "Y4_11") (pintype "output"))
    )
    (net (code "192") (name "unconnected-(U17A-Y5-Pad10)") (class "Default")
      (node (ref "U17") (pin "10") (pinfunction "Y5_10") (pintype "output"))
    )
    (net (code "193") (name "unconnected-(U17A-Y6-Pad9)") (class "Default")
      (node (ref "U17") (pin "9") (pinfunction "Y6_9") (pintype "output"))
    )
    (net (code "194") (name "unconnected-(U17A-Y7-Pad7)") (class "Default")
      (node (ref "U17") (pin "7") (pinfunction "Y7_7") (pintype "output"))
    )
    (net (code "195") (name "unconnected-(U18A-Y0-Pad15)") (class "Default")
      (node (ref "U18") (pin "15") (pinfunction "Y0_15") (pintype "output"))
    )
    (net (code "196") (name "unconnected-(U18A-Y1-Pad14)") (class "Default")
      (node (ref "U18") (pin "14") (pinfunction "Y1_14") (pintype "output"))
    )
    (net (code "197") (name "unconnected-(U18A-Y2-Pad13)") (class "Default")
      (node (ref "U18") (pin "13") (pinfunction "Y2_13") (pintype "output"))
    )
    (net (code "198") (name "unconnected-(U18A-Y3-Pad12)") (class "Default")
      (node (ref "U18") (pin "12") (pinfunction "Y3_12") (pintype "output"))
    )
    (net (code "199") (name "unconnected-(U18A-Y5-Pad10)") (class "Default")
      (node (ref "U18") (pin "10") (pinfunction "Y5_10") (pintype "output"))
    )
    (net (code "200") (name "unconnected-(U18A-Y6-Pad9)") (class "Default")
      (node (ref "U18") (pin "9") (pinfunction "Y6_9") (pintype "output"))
    )
    (net (code "201") (name "unconnected-(U18A-Y7-Pad7)") (class "Default")
      (node (ref "U18") (pin "7") (pinfunction "Y7_7") (pintype "output"))
    )
    (net (code "202") (name "unconnected-(U23A-1Q-Pad19)") (class "Default")
      (node (ref "U23") (pin "19") (pinfunction "1Q_19") (pintype "tri_state"))
    )
    (net (code "203") (name "unconnected-(U23A-2Q-Pad18)") (class "Default")
      (node (ref "U23") (pin "18") (pinfunction "2Q_18") (pintype "tri_state"))
    )
    (net (code "204") (name "unconnected-(U23A-3Q-Pad17)") (class "Default")
      (node (ref "U23") (pin "17") (pinfunction "3Q_17") (pintype "tri_state"))
    )
    (net (code "205") (name "unconnected-(U23A-4Q-Pad16)") (class "Default")
      (node (ref "U23") (pin "16") (pinfunction "4Q_16") (pintype "tri_state"))
    )
    (net (code "206") (name "unconnected-(U23A-5Q-Pad15)") (class "Default")
      (node (ref "U23") (pin "15") (pinfunction "5Q_15") (pintype "tri_state"))
    )
    (net (code "207") (name "unconnected-(U23A-6Q-Pad14)") (class "Default")
      (node (ref "U23") (pin "14") (pinfunction "6Q_14") (pintype "tri_state"))
    )
    (net (code "208") (name "unconnected-(U23A-7Q-Pad13)") (class "Default")
      (node (ref "U23") (pin "13") (pinfunction "7Q_13") (pintype "tri_state"))
    )
    (net (code "209") (name "unconnected-(Y1-TS-Pad1)") (class "Default")
      (node (ref "Y1") (pin "1") (pinfunction "TS_1") (pintype "passive"))
    )
  )
)
